# MAIN.net
KiCad netlist of a schematic drawn in Altium Designer
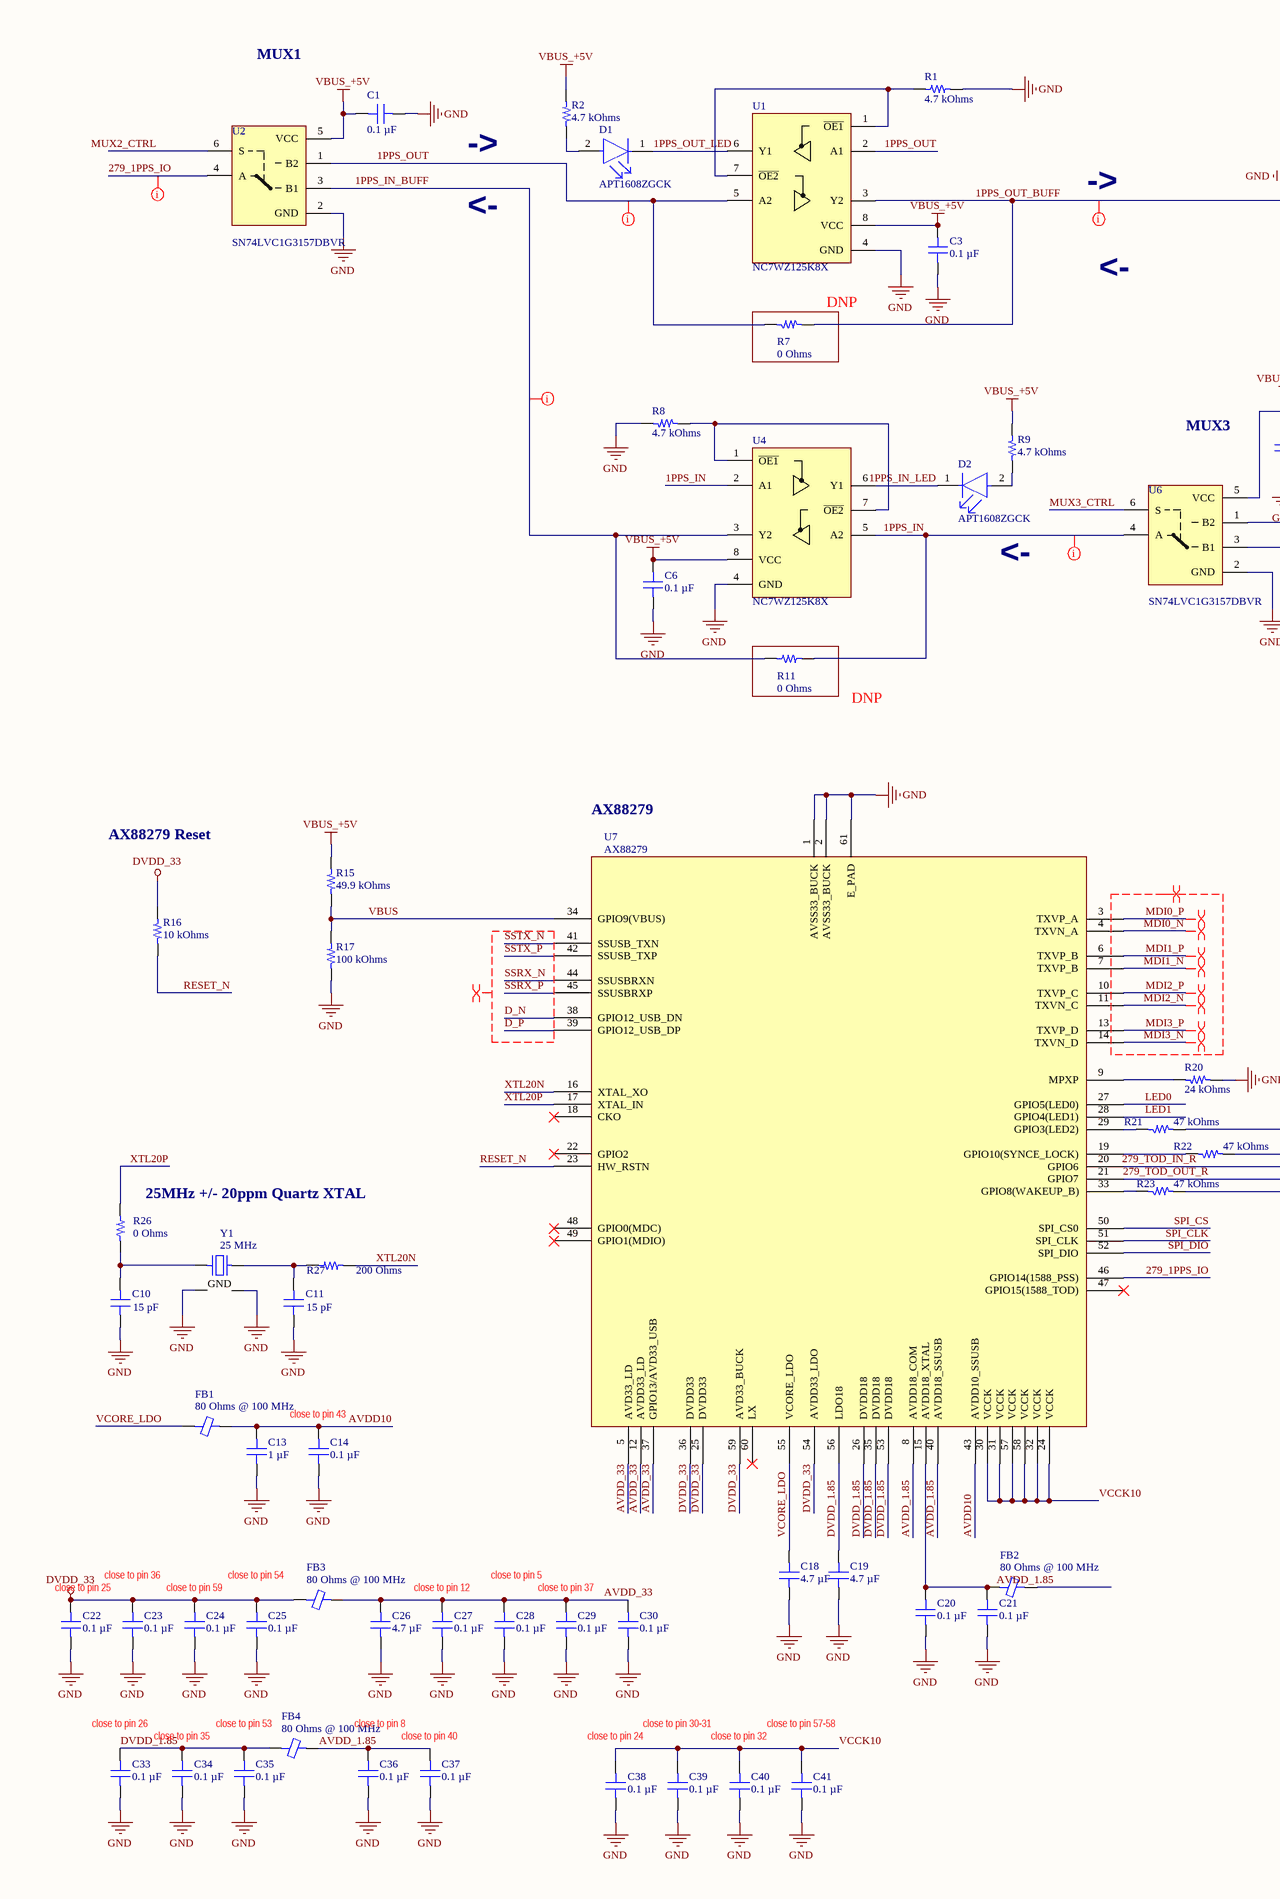
[diagram p0: MAIN.SchDoc, left]
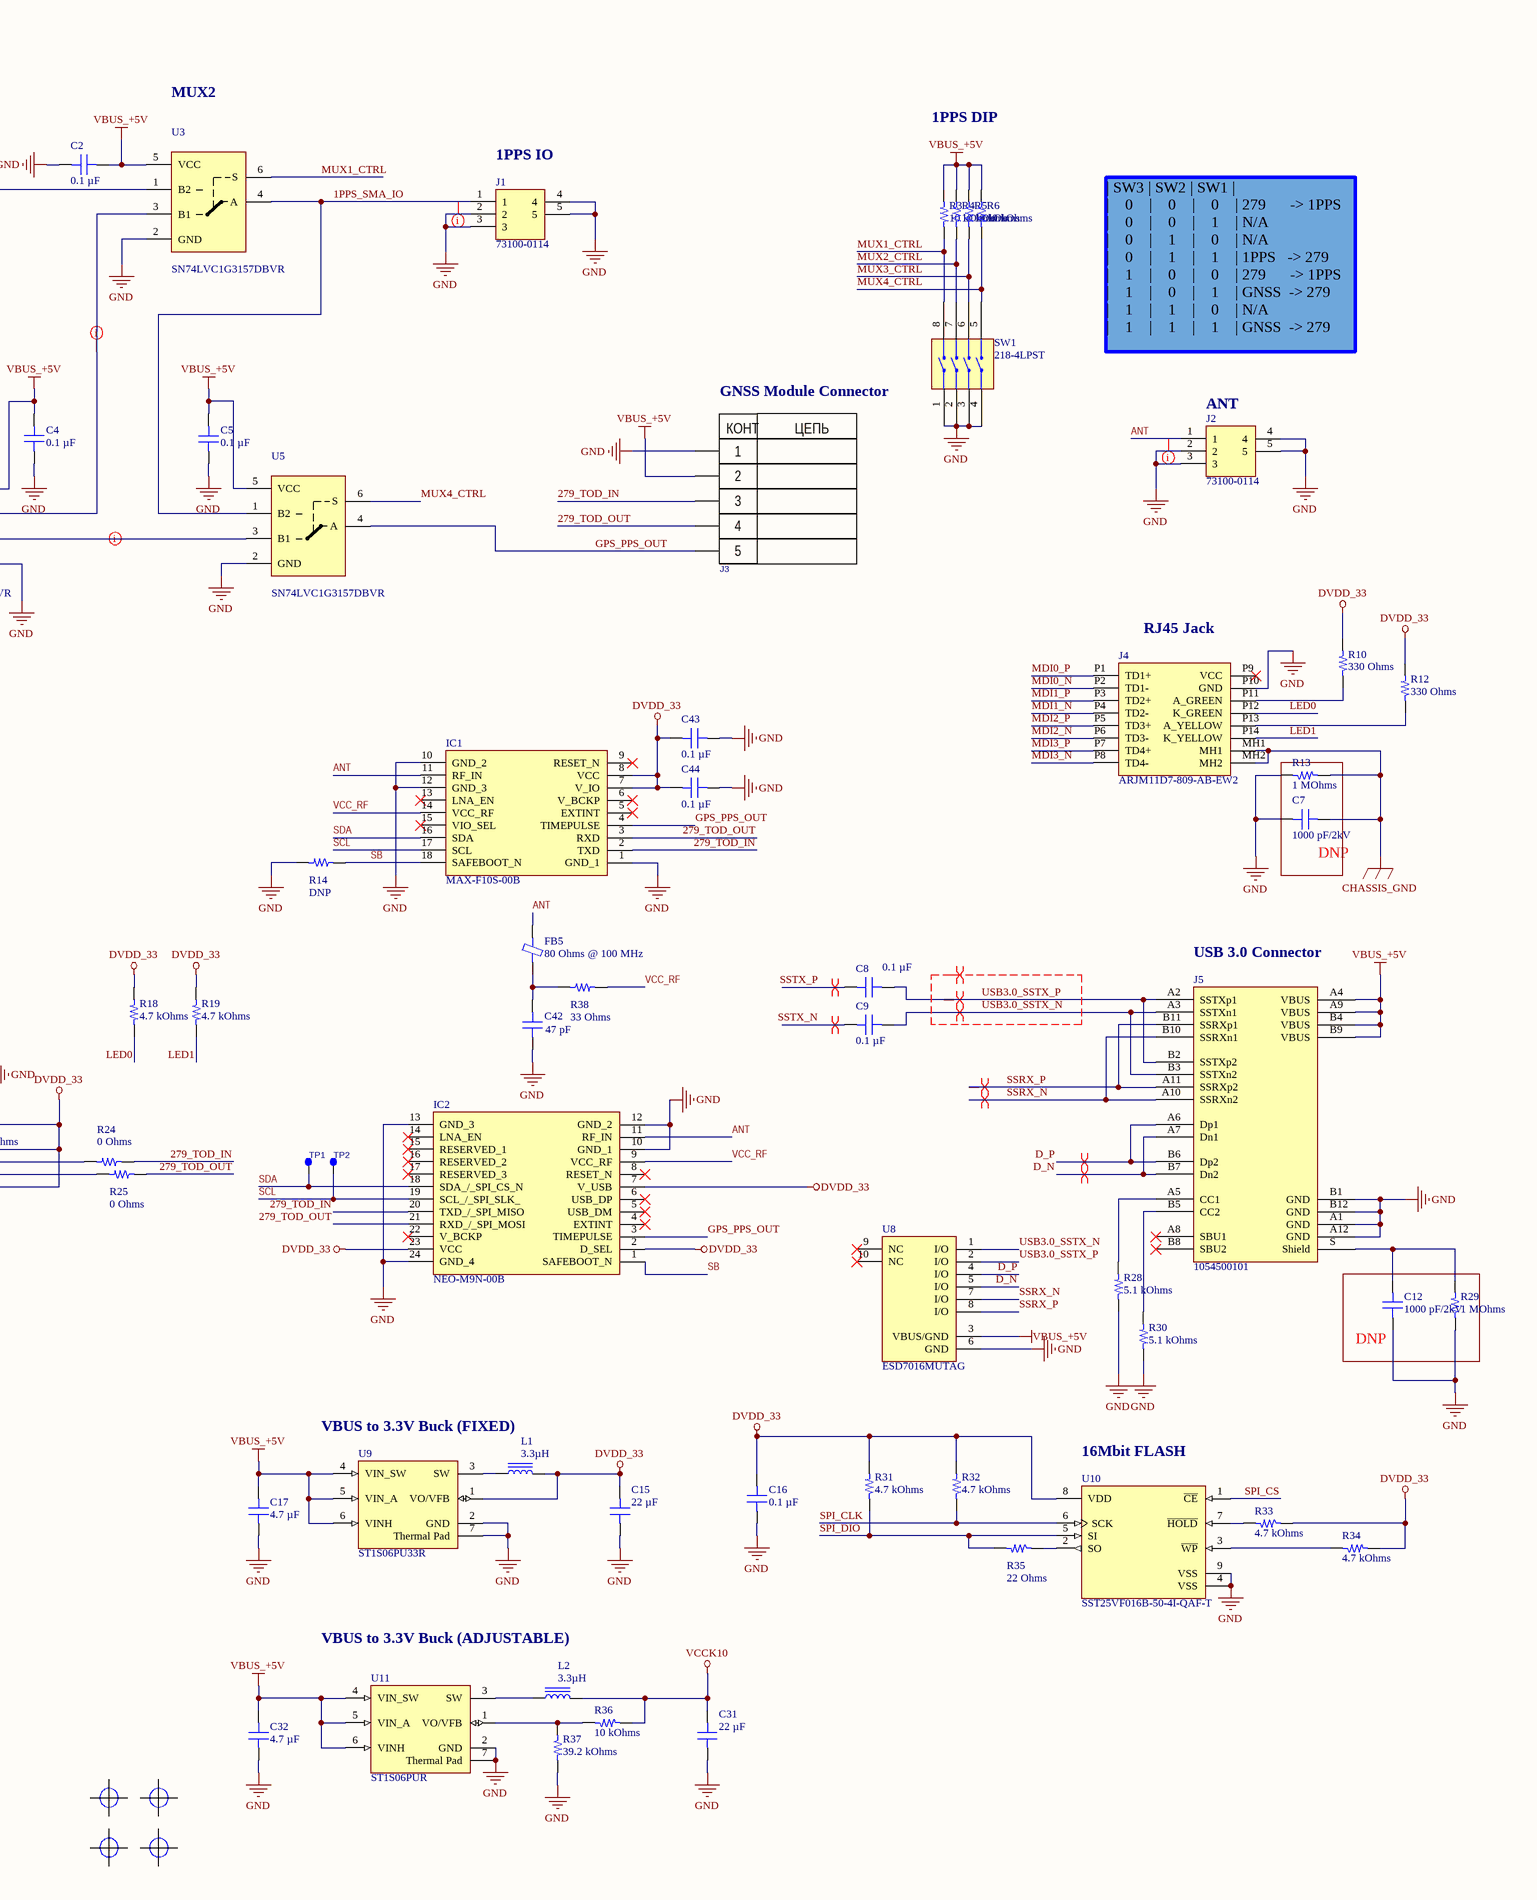
[diagram p1: MAIN.SchDoc, right]

(export (version "E")
  (design (tool "Eeschema 10.0.6"))
  (components
    (comp (ref "C1")
      (value "0.1 µF")
      (footprint "CAP 0402_1005")
      (description "CAP CER 0.1UF 10V X7R 0402")
      (fields (field (name "TOLERANCE") "±10%") (field (name "MANUFACTURER") "Yageo"))
      (libsource (lib "Celestial Altium Library - altium_library") (part "Capacitor"))
    )
    (comp (ref "C2")
      (value "0.1 µF")
      (footprint "CAP 0402_1005")
      (description "CAP CER 0.1UF 10V X7R 0402")
      (fields (field (name "TOLERANCE") "±10%") (field (name "MANUFACTURER") "Yageo"))
      (libsource (lib "Celestial Altium Library - altium_library") (part "Capacitor"))
    )
    (comp (ref "C3")
      (value "0.1 µF")
      (footprint "CAP 0402_1005")
      (description "CAP CER 0.1UF 10V X7R 0402")
      (fields (field (name "TOLERANCE") "±10%") (field (name "MANUFACTURER") "Yageo"))
      (libsource (lib "Celestial Altium Library - altium_library") (part "Capacitor"))
    )
    (comp (ref "C4")
      (value "0.1 µF")
      (footprint "CAP 0402_1005")
      (description "CAP CER 0.1UF 10V X7R 0402")
      (fields (field (name "TOLERANCE") "±10%") (field (name "MANUFACTURER") "Yageo"))
      (libsource (lib "Celestial Altium Library - altium_library") (part "Capacitor"))
    )
    (comp (ref "C5")
      (value "0.1 µF")
      (footprint "CAP 0402_1005")
      (description "CAP CER 0.1UF 10V X7R 0402")
      (fields (field (name "TOLERANCE") "±10%") (field (name "MANUFACTURER") "Yageo"))
      (libsource (lib "Celestial Altium Library - altium_library") (part "Capacitor"))
    )
    (comp (ref "C6")
      (value "0.1 µF")
      (footprint "CAP 0402_1005")
      (description "CAP CER 0.1UF 10V X7R 0402")
      (fields (field (name "TOLERANCE") "±10%") (field (name "MANUFACTURER") "Yageo"))
      (libsource (lib "Celestial Altium Library - altium_library") (part "Capacitor"))
    )
    (comp (ref "C7")
      (value "1000 pF/2kV")
      (footprint "CAP 1206_3216 - 0.8MM")
      (description "CAP CER 1000PF 2KV X7R 1206")
      (fields (field (name "PART NUMBER") "CC1206KKX7RDBB102") (field (name "MANUFACTURER") "Yageo"))
      (libsource (lib "Celestial Altium Library - altium_library") (part "Capacitor"))
    )
    (comp (ref "C8")
      (value "0.1 µF")
      (footprint "CAP 0402_1005")
      (description "CAP CER 0.1UF 10V X7R 0402")
      (fields (field (name "TOLERANCE") "±10%") (field (name "MANUFACTURER") "Yageo"))
      (libsource (lib "Celestial Altium Library - altium_library") (part "Capacitor"))
    )
    (comp (ref "C9")
      (value "0.1 µF")
      (footprint "CAP 0402_1005")
      (description "CAP CER 0.1UF 10V X7R 0402")
      (fields (field (name "TOLERANCE") "±10%") (field (name "MANUFACTURER") "Yageo"))
      (libsource (lib "Celestial Altium Library - altium_library") (part "Capacitor"))
    )
    (comp (ref "C10")
      (value "15 pF")
      (footprint "CAP 0402_1005")
      (description "CAP CER 15PF 50V C0G/NPO 0402")
      (fields (field (name "MANUFACTURER") "Yageo") (field (name "TOLERANCE") "±10%"))
      (libsource (lib "Celestial Altium Library - altium_library") (part "Capacitor"))
    )
    (comp (ref "C11")
      (value "15 pF")
      (footprint "CAP 0402_1005")
      (description "CAP CER 15PF 50V C0G/NPO 0402")
      (fields (field (name "MANUFACTURER") "Yageo") (field (name "TOLERANCE") "±10%"))
      (libsource (lib "Celestial Altium Library - altium_library") (part "Capacitor"))
    )
    (comp (ref "C12")
      (value "1000 pF/2kV")
      (footprint "CAP 1206_3216 - 0.8MM")
      (description "CAP CER 1000PF 2KV X7R 1206")
      (fields (field (name "PART NUMBER") "CC1206KKX7RDBB102") (field (name "MANUFACTURER") "Yageo"))
      (libsource (lib "Celestial Altium Library - altium_library") (part "Capacitor"))
    )
    (comp (ref "C13")
      (value "1 µF")
      (footprint "CAP 0402_1005")
      (description "CAP CER 1UF 10V X5R 0402")
      (fields (field (name "TOLERANCE") "±10%") (field (name "MANUFACTURER") "Yageo"))
      (libsource (lib "Celestial Altium Library - altium_library") (part "Capacitor"))
    )
    (comp (ref "C14")
      (value "0.1 µF")
      (footprint "CAP 0402_1005")
      (description "CAP CER 0.1UF 10V X7R 0402")
      (fields (field (name "TOLERANCE") "±10%") (field (name "MANUFACTURER") "Yageo"))
      (libsource (lib "Celestial Altium Library - altium_library") (part "Capacitor"))
    )
    (comp (ref "C15")
      (value "22 µF")
      (footprint "CAP 0603_1608")
      (description "CAP CER 22UF 10V X5R 0603")
      (fields (field (name "MANUFACTURER") "Yageo") (field (name "TOLERANCE") "±20%"))
      (libsource (lib "Celestial Altium Library - altium_library") (part "Capacitor"))
    )
    (comp (ref "C16")
      (value "0.1 µF")
      (footprint "CAP 0402_1005")
      (description "CAP CER 0.1UF 10V X7R 0402")
      (fields (field (name "TOLERANCE") "±10%") (field (name "MANUFACTURER") "Yageo"))
      (libsource (lib "Celestial Altium Library - altium_library") (part "Capacitor"))
    )
    (comp (ref "C17")
      (value "4.7 µF")
      (footprint "CAP 0402_1005")
      (description "CAP CER 4.7UF 10V X5R 0402")
      (fields (field (name "TOLERANCE") "±20%") (field (name "MANUFACTURER") "Yageo"))
      (libsource (lib "Celestial Altium Library - altium_library") (part "Capacitor"))
    )
    (comp (ref "C18")
      (value "4.7 µF")
      (footprint "CAP 0402_1005")
      (description "CAP CER 4.7UF 10V X5R 0402")
      (fields (field (name "TOLERANCE") "±20%") (field (name "MANUFACTURER") "Yageo"))
      (libsource (lib "Celestial Altium Library - altium_library") (part "Capacitor"))
    )
    (comp (ref "C19")
      (value "4.7 µF")
      (footprint "CAP 0402_1005")
      (description "CAP CER 4.7UF 10V X5R 0402")
      (fields (field (name "TOLERANCE") "±20%") (field (name "MANUFACTURER") "Yageo"))
      (libsource (lib "Celestial Altium Library - altium_library") (part "Capacitor"))
    )
    (comp (ref "C20")
      (value "0.1 µF")
      (footprint "CAP 0402_1005")
      (description "CAP CER 0.1UF 10V X7R 0402")
      (fields (field (name "TOLERANCE") "±10%") (field (name "MANUFACTURER") "Yageo"))
      (libsource (lib "Celestial Altium Library - altium_library") (part "Capacitor"))
    )
    (comp (ref "C21")
      (value "0.1 µF")
      (footprint "CAP 0402_1005")
      (description "CAP CER 0.1UF 10V X7R 0402")
      (fields (field (name "TOLERANCE") "±10%") (field (name "MANUFACTURER") "Yageo"))
      (libsource (lib "Celestial Altium Library - altium_library") (part "Capacitor"))
    )
    (comp (ref "C22")
      (value "0.1 µF")
      (footprint "CAP 0402_1005")
      (description "CAP CER 0.1UF 10V X7R 0402")
      (fields (field (name "TOLERANCE") "±10%") (field (name "MANUFACTURER") "Yageo"))
      (libsource (lib "Celestial Altium Library - altium_library") (part "Capacitor"))
    )
    (comp (ref "C23")
      (value "0.1 µF")
      (footprint "CAP 0402_1005")
      (description "CAP CER 0.1UF 10V X7R 0402")
      (fields (field (name "TOLERANCE") "±10%") (field (name "MANUFACTURER") "Yageo"))
      (libsource (lib "Celestial Altium Library - altium_library") (part "Capacitor"))
    )
    (comp (ref "C24")
      (value "0.1 µF")
      (footprint "CAP 0402_1005")
      (description "CAP CER 0.1UF 10V X7R 0402")
      (fields (field (name "TOLERANCE") "±10%") (field (name "MANUFACTURER") "Yageo"))
      (libsource (lib "Celestial Altium Library - altium_library") (part "Capacitor"))
    )
    (comp (ref "C25")
      (value "0.1 µF")
      (footprint "CAP 0402_1005")
      (description "CAP CER 0.1UF 10V X7R 0402")
      (fields (field (name "TOLERANCE") "±10%") (field (name "MANUFACTURER") "Yageo"))
      (libsource (lib "Celestial Altium Library - altium_library") (part "Capacitor"))
    )
    (comp (ref "C26")
      (value "4.7 µF")
      (footprint "CAP 0402_1005")
      (description "CAP CER 4.7UF 10V X5R 0402")
      (fields (field (name "TOLERANCE") "±20%") (field (name "MANUFACTURER") "Yageo"))
      (libsource (lib "Celestial Altium Library - altium_library") (part "Capacitor"))
    )
    (comp (ref "C27")
      (value "0.1 µF")
      (footprint "CAP 0402_1005")
      (description "CAP CER 0.1UF 10V X7R 0402")
      (fields (field (name "TOLERANCE") "±10%") (field (name "MANUFACTURER") "Yageo"))
      (libsource (lib "Celestial Altium Library - altium_library") (part "Capacitor"))
    )
    (comp (ref "C28")
      (value "0.1 µF")
      (footprint "CAP 0402_1005")
      (description "CAP CER 0.1UF 10V X7R 0402")
      (fields (field (name "TOLERANCE") "±10%") (field (name "MANUFACTURER") "Yageo"))
      (libsource (lib "Celestial Altium Library - altium_library") (part "Capacitor"))
    )
    (comp (ref "C29")
      (value "0.1 µF")
      (footprint "CAP 0402_1005")
      (description "CAP CER 0.1UF 10V X7R 0402")
      (fields (field (name "TOLERANCE") "±10%") (field (name "MANUFACTURER") "Yageo"))
      (libsource (lib "Celestial Altium Library - altium_library") (part "Capacitor"))
    )
    (comp (ref "C30")
      (value "0.1 µF")
      (footprint "CAP 0402_1005")
      (description "CAP CER 0.1UF 10V X7R 0402")
      (fields (field (name "TOLERANCE") "±10%") (field (name "MANUFACTURER") "Yageo"))
      (libsource (lib "Celestial Altium Library - altium_library") (part "Capacitor"))
    )
    (comp (ref "C31")
      (value "22 µF")
      (footprint "CAP 0603_1608")
      (description "CAP CER 22UF 10V X5R 0603")
      (fields (field (name "MANUFACTURER") "Yageo") (field (name "TOLERANCE") "±20%"))
      (libsource (lib "Celestial Altium Library - altium_library") (part "Capacitor"))
    )
    (comp (ref "C32")
      (value "4.7 µF")
      (footprint "CAP 0402_1005")
      (description "CAP CER 4.7UF 10V X5R 0402")
      (fields (field (name "TOLERANCE") "±20%") (field (name "MANUFACTURER") "Yageo"))
      (libsource (lib "Celestial Altium Library - altium_library") (part "Capacitor"))
    )
    (comp (ref "C33")
      (value "0.1 µF")
      (footprint "CAP 0402_1005")
      (description "CAP CER 0.1UF 10V X7R 0402")
      (fields (field (name "TOLERANCE") "±10%") (field (name "MANUFACTURER") "Yageo"))
      (libsource (lib "Celestial Altium Library - altium_library") (part "Capacitor"))
    )
    (comp (ref "C34")
      (value "0.1 µF")
      (footprint "CAP 0402_1005")
      (description "CAP CER 0.1UF 10V X7R 0402")
      (fields (field (name "TOLERANCE") "±10%") (field (name "MANUFACTURER") "Yageo"))
      (libsource (lib "Celestial Altium Library - altium_library") (part "Capacitor"))
    )
    (comp (ref "C35")
      (value "0.1 µF")
      (footprint "CAP 0402_1005")
      (description "CAP CER 0.1UF 10V X7R 0402")
      (fields (field (name "TOLERANCE") "±10%") (field (name "MANUFACTURER") "Yageo"))
      (libsource (lib "Celestial Altium Library - altium_library") (part "Capacitor"))
    )
    (comp (ref "C36")
      (value "0.1 µF")
      (footprint "CAP 0402_1005")
      (description "CAP CER 0.1UF 10V X7R 0402")
      (fields (field (name "TOLERANCE") "±10%") (field (name "MANUFACTURER") "Yageo"))
      (libsource (lib "Celestial Altium Library - altium_library") (part "Capacitor"))
    )
    (comp (ref "C37")
      (value "0.1 µF")
      (footprint "CAP 0402_1005")
      (description "CAP CER 0.1UF 10V X7R 0402")
      (fields (field (name "TOLERANCE") "±10%") (field (name "MANUFACTURER") "Yageo"))
      (libsource (lib "Celestial Altium Library - altium_library") (part "Capacitor"))
    )
    (comp (ref "C38")
      (value "0.1 µF")
      (footprint "CAP 0402_1005")
      (description "CAP CER 0.1UF 10V X7R 0402")
      (fields (field (name "TOLERANCE") "±10%") (field (name "MANUFACTURER") "Yageo"))
      (libsource (lib "Celestial Altium Library - altium_library") (part "Capacitor"))
    )
    (comp (ref "C39")
      (value "0.1 µF")
      (footprint "CAP 0402_1005")
      (description "CAP CER 0.1UF 10V X7R 0402")
      (fields (field (name "TOLERANCE") "±10%") (field (name "MANUFACTURER") "Yageo"))
      (libsource (lib "Celestial Altium Library - altium_library") (part "Capacitor"))
    )
    (comp (ref "C40")
      (value "0.1 µF")
      (footprint "CAP 0402_1005")
      (description "CAP CER 0.1UF 10V X7R 0402")
      (fields (field (name "TOLERANCE") "±10%") (field (name "MANUFACTURER") "Yageo"))
      (libsource (lib "Celestial Altium Library - altium_library") (part "Capacitor"))
    )
    (comp (ref "C41")
      (value "0.1 µF")
      (footprint "CAP 0402_1005")
      (description "CAP CER 0.1UF 10V X7R 0402")
      (fields (field (name "TOLERANCE") "±10%") (field (name "MANUFACTURER") "Yageo"))
      (libsource (lib "Celestial Altium Library - altium_library") (part "Capacitor"))
    )
    (comp (ref "C42")
      (value "47 pF")
      (footprint "CAP 0402_1005")
      (description "CAP CER 47PF 50V C0G/NPO 0402")
      (fields (field (name "MANUFACTURER") "Yageo") (field (name "TOLERANCE") "±10%"))
      (libsource (lib "Celestial Altium Library - altium_library") (part "Capacitor"))
    )
    (comp (ref "C43")
      (value "0.1 µF")
      (footprint "CAP 0402_1005")
      (description "CAP CER 0.1UF 10V X7R 0402")
      (fields (field (name "TOLERANCE") "±10%") (field (name "MANUFACTURER") "Yageo"))
      (libsource (lib "Celestial Altium Library - altium_library") (part "Capacitor"))
    )
    (comp (ref "C44")
      (value "0.1 µF")
      (footprint "CAP 0402_1005")
      (description "CAP CER 0.1UF 10V X7R 0402")
      (fields (field (name "TOLERANCE") "±10%") (field (name "MANUFACTURER") "Yageo"))
      (libsource (lib "Celestial Altium Library - altium_library") (part "Capacitor"))
    )
    (comp (ref "D1")
      (value "APT1608ZGCK")
      (footprint "FP-APT1608ZGCK-MFG")
      (description "LED GREEN CLEAR CHIP SMD")
      (fields (field (name "MANUFACTURER") "Kingbright"))
      (libsource (lib "Altium Content Vault") (part "8706943c75ba83719d021d2fdc84c58"))
    )
    (comp (ref "D2")
      (value "APT1608ZGCK")
      (footprint "FP-APT1608ZGCK-MFG")
      (description "LED GREEN CLEAR CHIP SMD")
      (fields (field (name "MANUFACTURER") "Kingbright"))
      (libsource (lib "Altium Content Vault") (part "8706943c75ba83719d021d2fdc84c58"))
    )
    (comp (ref "FB1")
      (value "80 Ohms @ 100 MHz")
      (footprint "FER 0402_1005")
      (description "FERRITE BEAD 80 OHM 0402 1LN")
      (fields
        (field (name "MANUFACTURER") "Murata Electronics")
        (field (name "PART NUMBER") "BLM15PD800SN1D")
      )
      (libsource (lib "Celestial Altium Library - altium_library") (part "Ferrite Chip"))
    )
    (comp (ref "FB2")
      (value "80 Ohms @ 100 MHz")
      (footprint "FER 0402_1005")
      (description "FERRITE BEAD 80 OHM 0402 1LN")
      (fields
        (field (name "MANUFACTURER") "Murata Electronics")
        (field (name "PART NUMBER") "BLM15PD800SN1D")
      )
      (libsource (lib "Celestial Altium Library - altium_library") (part "Ferrite Chip"))
    )
    (comp (ref "FB3")
      (value "80 Ohms @ 100 MHz")
      (footprint "FER 0402_1005")
      (description "FERRITE BEAD 80 OHM 0402 1LN")
      (fields
        (field (name "MANUFACTURER") "Murata Electronics")
        (field (name "PART NUMBER") "BLM15PD800SN1D")
      )
      (libsource (lib "Celestial Altium Library - altium_library") (part "Ferrite Chip"))
    )
    (comp (ref "FB4")
      (value "80 Ohms @ 100 MHz")
      (footprint "FER 0402_1005")
      (description "FERRITE BEAD 80 OHM 0402 1LN")
      (fields
        (field (name "MANUFACTURER") "Murata Electronics")
        (field (name "PART NUMBER") "BLM15PD800SN1D")
      )
      (libsource (lib "Celestial Altium Library - altium_library") (part "Ferrite Chip"))
    )
    (comp (ref "FB5")
      (value "80 Ohms @ 100 MHz")
      (footprint "FER 0402_1005")
      (description "FERRITE BEAD 80 OHM 0402 1LN")
      (fields
        (field (name "MANUFACTURER") "Murata Electronics")
        (field (name "PART NUMBER") "BLM15PD800SN1D")
      )
      (libsource (lib "Celestial Altium Library - altium_library") (part "Ferrite Chip"))
    )
    (comp (ref "IC1")
      (value "MAX-F10S-00B")
      (footprint "SamacSys:MAXF10S00B")
      (description "Integrated Circuit")
      (libsource (lib "SamacSys") (part "MAX-F10S-00B"))
    )
    (comp (ref "IC2")
      (value "NEO-M9N-00B")
      (footprint "SamacSys:NEOM9N00B")
      (description "Integrated Circuit")
      (fields (field (name "MOUSER PART NUMBER") "377-NEO-M9N-00B"))
      (libsource (lib "SamacSys") (part "NEO-M9N-00B"))
    )
    (comp (ref "J1")
      (value "73100-0114")
      (footprint "SamacSys:731000114")
      (description "Connector")
      (fields (field (name "MOUSER PART NUMBER") "538-73100-0114"))
      (libsource (lib "SamacSys") (part "73100-0114"))
    )
    (comp (ref "J2")
      (value "73100-0114")
      (footprint "SamacSys:731000114")
      (description "Connector")
      (fields (field (name "MOUSER PART NUMBER") "538-73100-0114"))
      (libsource (lib "SamacSys") (part "73100-0114"))
    )
    (comp (ref "J3")
      (value "PBS-5")
      (footprint "SamacSys:PBS-5")
      (description "Connector")
      (fields (field (name "MANUFACTURER") "Connfly") (field (name "PART NUMBER") "PBD-5"))
      (libsource (lib "SamacSys") (part "PBS-5"))
    )
    (comp (ref "J4")
      (value "ARJM11D7-809-AB-EW2")
      (footprint "SamacSys:ARJM11D7809ABEW2")
      (description "Connector")
      (fields (field (name "MOUSER PART NUMBER") "815-RJM11D7809ABEW2"))
      (libsource (lib "*") (part "ARJM11D7-809-AB-EW2"))
    )
    (comp (ref "J5")
      (value "1054500101")
      (footprint "Molex 1054500101")
      (description "CONN RCP USB3.1 TYPEC 24P SMD RA")
      (fields (field (name "MANUFACTURER") "Molex"))
      (libsource (lib "Celestial Altium Library - altium_library") (part "USB 3.0 Type C"))
    )
    (comp (ref "L1")
      (value "3.3µH")
      (footprint "IND 1008_2520")
      (description "FIXED IND 3.3UH 1.2A 100 MOHM")
      (fields (field (name "TOLERANCE") "±20%") (field (name "MANUFACTURER") "Murata Electronics"))
      (libsource (lib "Celestial Altium Library - altium_library") (part "Inductor"))
    )
    (comp (ref "L2")
      (value "3.3µH")
      (footprint "IND 1008_2520")
      (description "FIXED IND 3.3UH 1.2A 100 MOHM")
      (fields (field (name "TOLERANCE") "±20%") (field (name "MANUFACTURER") "Murata Electronics"))
      (libsource (lib "Celestial Altium Library - altium_library") (part "Inductor"))
    )
    (comp (ref "MNT1")
      (value "MOUNT_HOLE")
      (footprint "SamacSys:MOUNT_3mm")
      (description "Mount hole")
      (libsource (lib "SamacSys") (part "MOUNT_HOLE"))
    )
    (comp (ref "MNT2")
      (value "MOUNT_HOLE")
      (footprint "SamacSys:MOUNT_3mm")
      (description "Mount hole")
      (libsource (lib "SamacSys") (part "MOUNT_HOLE"))
    )
    (comp (ref "MNT3")
      (value "MOUNT_HOLE")
      (footprint "SamacSys:MOUNT_3mm")
      (description "Mount hole")
      (libsource (lib "SamacSys") (part "MOUNT_HOLE"))
    )
    (comp (ref "MNT4")
      (value "MOUNT_HOLE")
      (footprint "SamacSys:MOUNT_3mm")
      (description "Mount hole")
      (libsource (lib "SamacSys") (part "MOUNT_HOLE"))
    )
    (comp (ref "R1")
      (value "4.7 kOhms")
      (footprint "YAGEO RES 0402_1005")
      (description "RES 4.7K OHM 1% 1/16W 0402")
      (fields (field (name "TOLERANCE") "±1%") (field (name "MANUFACTURER") "Yageo"))
      (libsource (lib "Celestial Altium Library - altium_library") (part "Resistor"))
    )
    (comp (ref "R2")
      (value "4.7 kOhms")
      (footprint "YAGEO RES 0402_1005")
      (description "RES 4.7K OHM 1% 1/16W 0402")
      (fields (field (name "TOLERANCE") "±1%") (field (name "MANUFACTURER") "Yageo"))
      (libsource (lib "Celestial Altium Library - altium_library") (part "Resistor"))
    )
    (comp (ref "R3")
      (value "10 kOhms")
      (footprint "YAGEO RES 0402_1005")
      (description "RES 10K OHM 1% 1/16W 0402")
      (fields (field (name "TOLERANCE") "±1%") (field (name "MANUFACTURER") "Yageo"))
      (libsource (lib "Celestial Altium Library - altium_library") (part "Resistor"))
    )
    (comp (ref "R4")
      (value "10 kOhms")
      (footprint "YAGEO RES 0402_1005")
      (description "RES 10K OHM 1% 1/16W 0402")
      (fields (field (name "TOLERANCE") "±1%") (field (name "MANUFACTURER") "Yageo"))
      (libsource (lib "Celestial Altium Library - altium_library") (part "Resistor"))
    )
    (comp (ref "R5")
      (value "10 kOhms")
      (footprint "YAGEO RES 0402_1005")
      (description "RES 10K OHM 1% 1/16W 0402")
      (fields (field (name "TOLERANCE") "±1%") (field (name "MANUFACTURER") "Yageo"))
      (libsource (lib "Celestial Altium Library - altium_library") (part "Resistor"))
    )
    (comp (ref "R6")
      (value "10 kOhms")
      (footprint "YAGEO RES 0402_1005")
      (description "RES 10K OHM 1% 1/16W 0402")
      (fields (field (name "TOLERANCE") "±1%") (field (name "MANUFACTURER") "Yageo"))
      (libsource (lib "Celestial Altium Library - altium_library") (part "Resistor"))
    )
    (comp (ref "R7")
      (value "0 Ohms")
      (footprint "YAGEO RES 0402_1005")
      (description "RES 0 OHM JUMPER 1/16W 0402")
      (fields (field (name "TOLERANCE") "Jumper") (field (name "MANUFACTURER") "Yageo"))
      (libsource (lib "Celestial Altium Library - altium_library") (part "Resistor"))
    )
    (comp (ref "R8")
      (value "4.7 kOhms")
      (footprint "YAGEO RES 0402_1005")
      (description "RES 4.7K OHM 1% 1/16W 0402")
      (fields (field (name "TOLERANCE") "±1%") (field (name "MANUFACTURER") "Yageo"))
      (libsource (lib "Celestial Altium Library - altium_library") (part "Resistor"))
    )
    (comp (ref "R9")
      (value "4.7 kOhms")
      (footprint "YAGEO RES 0402_1005")
      (description "RES 4.7K OHM 1% 1/16W 0402")
      (fields (field (name "TOLERANCE") "±1%") (field (name "MANUFACTURER") "Yageo"))
      (libsource (lib "Celestial Altium Library - altium_library") (part "Resistor"))
    )
    (comp (ref "R10")
      (value "330 Ohms")
      (footprint "YAGEO RES 0402_1005")
      (description "RES 330 OHM 1% 1/16W 0402")
      (fields (field (name "TOLERANCE") "±1%") (field (name "MANUFACTURER") "Yageo"))
      (libsource (lib "Celestial Altium Library - altium_library") (part "Resistor"))
    )
    (comp (ref "R11")
      (value "0 Ohms")
      (footprint "YAGEO RES 0402_1005")
      (description "RES 0 OHM JUMPER 1/16W 0402")
      (fields (field (name "TOLERANCE") "Jumper") (field (name "MANUFACTURER") "Yageo"))
      (libsource (lib "Celestial Altium Library - altium_library") (part "Resistor"))
    )
    (comp (ref "R12")
      (value "330 Ohms")
      (footprint "YAGEO RES 0402_1005")
      (description "RES 330 OHM 1% 1/16W 0402")
      (fields (field (name "TOLERANCE") "±1%") (field (name "MANUFACTURER") "Yageo"))
      (libsource (lib "Celestial Altium Library - altium_library") (part "Resistor"))
    )
    (comp (ref "R13")
      (value "1 MOhms")
      (footprint "YAGEO RES 0402_1005")
      (description "RES 1M OHM 1% 1/16W 0402")
      (fields (field (name "TOLERANCE") "±1%") (field (name "MANUFACTURER") "Yageo"))
      (libsource (lib "Celestial Altium Library - altium_library") (part "Resistor"))
    )
    (comp (ref "R14")
      (value "DNP")
      (footprint "YAGEO RES 0402_1005")
      (description "RES 0 OHM JUMPER 1/16W 0402")
      (fields (field (name "TOLERANCE") "Jumper") (field (name "MANUFACTURER") "Yageo"))
      (libsource (lib "Celestial Altium Library - altium_library") (part "Resistor"))
    )
    (comp (ref "R15")
      (value "49.9 kOhms")
      (footprint "YAGEO RES 0402_1005")
      (description "RES 49.9K OHM 1% 1/16W 0402")
      (fields (field (name "TOLERANCE") "±1%") (field (name "MANUFACTURER") "Yageo"))
      (libsource (lib "Celestial Altium Library - altium_library") (part "Resistor"))
    )
    (comp (ref "R16")
      (value "10 kOhms")
      (footprint "YAGEO RES 0402_1005")
      (description "RES 10K OHM 1% 1/16W 0402")
      (fields (field (name "TOLERANCE") "±1%") (field (name "MANUFACTURER") "Yageo"))
      (libsource (lib "Celestial Altium Library - altium_library") (part "Resistor"))
    )
    (comp (ref "R17")
      (value "100 kOhms")
      (footprint "YAGEO RES 0402_1005")
      (description "RES 100K OHM 1% 1/16W 0402")
      (fields (field (name "TOLERANCE") "±1%") (field (name "MANUFACTURER") "Yageo"))
      (libsource (lib "Celestial Altium Library - altium_library") (part "Resistor"))
    )
    (comp (ref "R18")
      (value "4.7 kOhms")
      (footprint "YAGEO RES 0402_1005")
      (description "RES 4.7K OHM 1% 1/16W 0402")
      (fields (field (name "TOLERANCE") "±1%") (field (name "MANUFACTURER") "Yageo"))
      (libsource (lib "Celestial Altium Library - altium_library") (part "Resistor"))
    )
    (comp (ref "R19")
      (value "4.7 kOhms")
      (footprint "YAGEO RES 0402_1005")
      (description "RES 4.7K OHM 1% 1/16W 0402")
      (fields (field (name "TOLERANCE") "±1%") (field (name "MANUFACTURER") "Yageo"))
      (libsource (lib "Celestial Altium Library - altium_library") (part "Resistor"))
    )
    (comp (ref "R20")
      (value "24 kOhms")
      (footprint "YAGEO RES 0402_1005")
      (description "RES 24K OHM 1% 1/16W 0402")
      (fields (field (name "TOLERANCE") "±1%") (field (name "MANUFACTURER") "Yageo"))
      (libsource (lib "Celestial Altium Library - altium_library") (part "Resistor"))
    )
    (comp (ref "R21")
      (value "47 kOhms")
      (footprint "YAGEO RES 0402_1005")
      (description "RES 47K OHM 1% 1/16W 0402")
      (fields (field (name "TOLERANCE") "±1%") (field (name "MANUFACTURER") "Yageo"))
      (libsource (lib "Celestial Altium Library - altium_library") (part "Resistor"))
    )
    (comp (ref "R22")
      (value "47 kOhms")
      (footprint "YAGEO RES 0402_1005")
      (description "RES 47K OHM 1% 1/16W 0402")
      (fields (field (name "TOLERANCE") "±1%") (field (name "MANUFACTURER") "Yageo"))
      (libsource (lib "Celestial Altium Library - altium_library") (part "Resistor"))
    )
    (comp (ref "R23")
      (value "47 kOhms")
      (footprint "YAGEO RES 0402_1005")
      (description "RES 47K OHM 1% 1/16W 0402")
      (fields (field (name "TOLERANCE") "±1%") (field (name "MANUFACTURER") "Yageo"))
      (libsource (lib "Celestial Altium Library - altium_library") (part "Resistor"))
    )
    (comp (ref "R24")
      (value "0 Ohms")
      (footprint "YAGEO RES 0402_1005")
      (description "RES 0 OHM JUMPER 1/16W 0402")
      (fields (field (name "TOLERANCE") "Jumper") (field (name "MANUFACTURER") "Yageo"))
      (libsource (lib "Celestial Altium Library - altium_library") (part "Resistor"))
    )
    (comp (ref "R25")
      (value "0 Ohms")
      (footprint "YAGEO RES 0402_1005")
      (description "RES 0 OHM JUMPER 1/16W 0402")
      (fields (field (name "TOLERANCE") "Jumper") (field (name "MANUFACTURER") "Yageo"))
      (libsource (lib "Celestial Altium Library - altium_library") (part "Resistor"))
    )
    (comp (ref "R26")
      (value "0 Ohms")
      (footprint "YAGEO RES 0402_1005")
      (description "RES 0 OHM JUMPER 1/16W 0402")
      (fields (field (name "TOLERANCE") "Jumper") (field (name "MANUFACTURER") "Yageo"))
      (libsource (lib "Celestial Altium Library - altium_library") (part "Resistor"))
    )
    (comp (ref "R27")
      (value "200 Ohms")
      (footprint "YAGEO RES 0402_1005")
      (description "RES 200 OHM 1% 1/16W 0402")
      (fields (field (name "MANUFACTURER") "Yageo") (field (name "PART NUMBER") "RC0402FR-07200RL"))
      (libsource (lib "Celestial Altium Library - altium_library") (part "Resistor"))
    )
    (comp (ref "R28")
      (value "5.1 kOhms")
      (footprint "YAGEO RES 0402_1005")
      (description "RES 5.1K OHM 1% 1/16W 0402")
      (fields (field (name "TOLERANCE") "±1%") (field (name "MANUFACTURER") "Yageo"))
      (libsource (lib "Celestial Altium Library - altium_library") (part "Resistor"))
    )
    (comp (ref "R29")
      (value "1 MOhms")
      (footprint "YAGEO RES 0402_1005")
      (description "RES 1M OHM 1% 1/16W 0402")
      (fields (field (name "TOLERANCE") "±1%") (field (name "MANUFACTURER") "Yageo"))
      (libsource (lib "Celestial Altium Library - altium_library") (part "Resistor"))
    )
    (comp (ref "R30")
      (value "5.1 kOhms")
      (footprint "YAGEO RES 0402_1005")
      (description "RES 5.1K OHM 1% 1/16W 0402")
      (fields (field (name "TOLERANCE") "±1%") (field (name "MANUFACTURER") "Yageo"))
      (libsource (lib "Celestial Altium Library - altium_library") (part "Resistor"))
    )
    (comp (ref "R31")
      (value "4.7 kOhms")
      (footprint "YAGEO RES 0402_1005")
      (description "RES 4.7K OHM 1% 1/16W 0402")
      (fields (field (name "TOLERANCE") "±1%") (field (name "MANUFACTURER") "Yageo"))
      (libsource (lib "Celestial Altium Library - altium_library") (part "Resistor"))
    )
    (comp (ref "R32")
      (value "4.7 kOhms")
      (footprint "YAGEO RES 0402_1005")
      (description "RES 4.7K OHM 1% 1/16W 0402")
      (fields (field (name "TOLERANCE") "±1%") (field (name "MANUFACTURER") "Yageo"))
      (libsource (lib "Celestial Altium Library - altium_library") (part "Resistor"))
    )
    (comp (ref "R33")
      (value "4.7 kOhms")
      (footprint "YAGEO RES 0402_1005")
      (description "RES 4.7K OHM 1% 1/16W 0402")
      (fields (field (name "TOLERANCE") "±1%") (field (name "MANUFACTURER") "Yageo"))
      (libsource (lib "Celestial Altium Library - altium_library") (part "Resistor"))
    )
    (comp (ref "R34")
      (value "4.7 kOhms")
      (footprint "YAGEO RES 0402_1005")
      (description "RES 4.7K OHM 1% 1/16W 0402")
      (fields (field (name "TOLERANCE") "±1%") (field (name "MANUFACTURER") "Yageo"))
      (libsource (lib "Celestial Altium Library - altium_library") (part "Resistor"))
    )
    (comp (ref "R35")
      (value "22 Ohms")
      (footprint "YAGEO RES 0402_1005")
      (description "RES 22 OHM 1% 1/16W 0402")
      (fields (field (name "TOLERANCE") "±1%") (field (name "MANUFACTURER") "Yageo"))
      (libsource (lib "Celestial Altium Library - altium_library") (part "Resistor"))
    )
    (comp (ref "R36")
      (value "10 kOhms")
      (footprint "YAGEO RES 0402_1005")
      (description "RES 10K OHM 1% 1/16W 0402")
      (fields (field (name "TOLERANCE") "±1%") (field (name "MANUFACTURER") "Yageo"))
      (libsource (lib "Celestial Altium Library - altium_library") (part "Resistor"))
    )
    (comp (ref "R37")
      (value "39.2 kOhms")
      (footprint "YAGEO RES 0402_1005")
      (description "RES 39.2K OHM 1% 1/16W 0402")
      (fields (field (name "TOLERANCE") "±1%") (field (name "MANUFACTURER") "Yageo"))
      (libsource (lib "Celestial Altium Library - altium_library") (part "Resistor"))
    )
    (comp (ref "R38")
      (value "33 Ohms")
      (footprint "YAGEO RES 0402_1005")
      (description "RES 33 OHM 1% 1/16W 0402")
      (fields (field (name "TOLERANCE") "±1%") (field (name "MANUFACTURER") "Yageo"))
      (libsource (lib "Celestial Altium Library - altium_library") (part "Resistor"))
    )
    (comp (ref "SW1")
      (value "218-4LPST")
      (footprint "CTS 218-4LPJ")
      (description "SWITCH SLIDE DIP SPST 25MA 24V")
      (fields (field (name "MANUFACTURER") "CTS Electrocomponents"))
      (libsource (lib "Celestial Altium Library - altium_library") (part "DIP SW 4P"))
    )
    (comp (ref "TP1")
      (value "PAD_TEST")
      (footprint "Samacsys:PAD_TEST")
      (description "Test Point")
      (fields (field (name "TOLERANCE") "{Tolerance}") (field (name "MANUFACTURER") "{Manufacturer}"))
      (libsource (lib "SamacSys") (part "PAD_TEST"))
    )
    (comp (ref "TP2")
      (value "PAD_TEST")
      (footprint "Samacsys:PAD_TEST")
      (description "Test Point")
      (fields (field (name "TOLERANCE") "{Tolerance}") (field (name "MANUFACTURER") "{Manufacturer}"))
      (libsource (lib "SamacSys") (part "PAD_TEST"))
    )
    (comp (ref "U1")
      (value "NC7WZ125K8X")
      (footprint "SamacSys:SOP50P310X90-8N")
      (description "Integrated Circuit")
      (libsource (lib "") (part "NC7WZ125K8X_1"))
    )
    (comp (ref "U2")
      (value "SN74LVC1G3157DBVR")
      (footprint "SamacSys:SOT95P280X145-6N")
      (description "Integrated Circuit")
      (fields (field (name "MOUSER PART NUMBER") "595-SN74LVC1G3157DBV"))
      (libsource (lib "") (part "SN74LVC1G3157DBVR_1"))
    )
    (comp (ref "U3")
      (value "SN74LVC1G3157DBVR")
      (footprint "SamacSys:SOT95P280X145-6N")
      (description "Integrated Circuit")
      (fields (field (name "MOUSER PART NUMBER") "595-SN74LVC1G3157DBV"))
      (libsource (lib "SamacSys") (part "SN74LVC1G3157DBVR"))
    )
    (comp (ref "U4")
      (value "NC7WZ125K8X")
      (footprint "SamacSys:SOP50P310X90-8N")
      (description "Integrated Circuit")
      (libsource (lib "SamacSys") (part "NC7WZ125K8X"))
    )
    (comp (ref "U5")
      (value "SN74LVC1G3157DBVR")
      (footprint "SamacSys:SOT95P280X145-6N")
      (description "Integrated Circuit")
      (fields (field (name "MOUSER PART NUMBER") "595-SN74LVC1G3157DBV"))
      (libsource (lib "SamacSys") (part "SN74LVC1G3157DBVR"))
    )
    (comp (ref "U6")
      (value "SN74LVC1G3157DBVR")
      (footprint "SamacSys:SOT95P280X145-6N")
      (description "Integrated Circuit")
      (fields (field (name "MOUSER PART NUMBER") "595-SN74LVC1G3157DBV"))
      (libsource (lib "") (part "SN74LVC1G3157DBVR_1"))
    )
    (comp (ref "U7")
      (value "AX88279")
      (footprint "IC_AX88279")
      (libsource (lib "LotusSound") (part "IC_AX88279"))
    )
    (comp (ref "U8")
      (value "ESD7016MUTAG")
      (footprint "ONSC-UDFN-8-517CB_V")
      (description "Low Capacitance ESD Protection USB 3.0, 8-Pin UDFN, Pb-Free, Tape and Reel")
      (fields (field (name "MANUFACTURER") "On Semiconductor"))
      (libsource (lib "Altium Content Vault") (part "ONSC-ESD7016-UDFN-8-517CB"))
    )
    (comp (ref "U9")
      (value "ST1S06PU33R")
      (footprint "DFN6D_L")
      (fields (field (name "MANUFACTURER") "STMicroelectronics"))
      (libsource (lib "Altium Content Vault") (part "PM-DCDC-ST1S06-IL7"))
    )
    (comp (ref "U10")
      (value "SST25VF016B-50-4I-QAF-T")
      (footprint "FP-C04-452-MFG")
      (libsource (lib "Altium Content Vault") (part "d7313dde12fd16fde488169701056cc"))
    )
    (comp (ref "U11")
      (value "ST1S06PUR")
      (footprint "DFN6D_M")
      (libsource (lib "Altium Content Vault") (part "PM-DCDC-ST1S06-IL7"))
    )
    (comp (ref "Y1")
      (value "25 MHz")
      (footprint "NDK NX3225GA")
      (description "CRYSTAL 25.0000MHZ 8PF SMD")
      (fields
        (field (name "MANUFACTURER") "NDK America, Inc.")
        (field (name "PART NUMBER") "NX3225GA-25.000M-STD-CRG-2")
      )
      (libsource (lib "Celestial Altium Library - altium_library") (part "NDK Crystal NX3225GA"))
    )
  )
  (nets
    (net (code "1") (name "/1PPS_IN") (class "Default")
      (node (ref "R11") (pin "1") (pinfunction "1_1") (pintype "passive"))
      (node (ref "U4") (pin "2") (pinfunction "A1_2") (pintype "passive"))
      (node (ref "U4") (pin "5") (pinfunction "A2_5") (pintype "passive"))
      (node (ref "U6") (pin "4") (pinfunction "A_4") (pintype "passive"))
    )
    (net (code "2") (name "/1PPS_IN_BUFF") (class "Default")
      (node (ref "R11") (pin "2") (pinfunction "2_2") (pintype "passive"))
      (node (ref "U2") (pin "3") (pinfunction "B1_3") (pintype "passive"))
      (node (ref "U4") (pin "3") (pinfunction "Y2_3") (pintype "passive"))
    )
    (net (code "3") (name "/1PPS_IN_LED") (class "Default")
      (node (ref "D2") (pin "1") (pinfunction "C_1") (pintype "passive"))
      (node (ref "U4") (pin "6") (pinfunction "Y1_6") (pintype "passive"))
    )
    (net (code "4") (name "/1PPS_OUT") (class "Default")
      (node (ref "R7") (pin "2") (pinfunction "2_2") (pintype "passive"))
      (node (ref "U1") (pin "2") (pinfunction "A1_2") (pintype "passive"))
      (node (ref "U1") (pin "5") (pinfunction "A2_5") (pintype "passive"))
      (node (ref "U2") (pin "1") (pinfunction "B2_1") (pintype "passive"))
    )
    (net (code "5") (name "/1PPS_OUT_BUFF") (class "Default")
      (node (ref "R7") (pin "1") (pinfunction "1_1") (pintype "passive"))
      (node (ref "U1") (pin "3") (pinfunction "Y2_3") (pintype "passive"))
      (node (ref "U3") (pin "1") (pinfunction "B2_1") (pintype "passive"))
    )
    (net (code "6") (name "/1PPS_OUT_LED") (class "Default")
      (node (ref "D1") (pin "1") (pinfunction "C_1") (pintype "passive"))
      (node (ref "U1") (pin "6") (pinfunction "Y1_6") (pintype "passive"))
    )
    (net (code "7") (name "/1PPS_SMA_IO") (class "Default")
      (node (ref "J1") (pin "1") (pinfunction "1_1") (pintype "passive"))
      (node (ref "U3") (pin "4") (pinfunction "A_4") (pintype "passive"))
      (node (ref "U5") (pin "1") (pinfunction "B2_1") (pintype "passive"))
    )
    (net (code "8") (name "/279_1PPS_IO") (class "Default")
      (node (ref "U2") (pin "4") (pinfunction "A_4") (pintype "passive"))
      (node (ref "U7") (pin "46") (pinfunction "GPIO14(1588_PSS)_46") (pintype "passive"))
    )
    (net (code "9") (name "/279_TOD_IN") (class "Default")
      (node (ref "IC1") (pin "2") (pinfunction "TXD_2") (pintype "passive"))
      (node (ref "IC2") (pin "20") (pinfunction "TXD_/_SPI_MISO_20") (pintype "passive"))
      (node (ref "J3") (pin "3") (pinfunction "3_3") (pintype "passive"))
      (node (ref "R24") (pin "1") (pinfunction "1_1") (pintype "passive"))
    )
    (net (code "10") (name "/279_TOD_IN_R") (class "Default")
      (node (ref "R24") (pin "2") (pinfunction "2_2") (pintype "passive"))
      (node (ref "U7") (pin "20") (pinfunction "GPIO6_20") (pintype "passive"))
    )
    (net (code "11") (name "/279_TOD_OUT") (class "Default")
      (node (ref "IC1") (pin "3") (pinfunction "RXD_3") (pintype "passive"))
      (node (ref "IC2") (pin "21") (pinfunction "RXD_/_SPI_MOSI_21") (pintype "passive"))
      (node (ref "J3") (pin "4") (pinfunction "4_4") (pintype "passive"))
      (node (ref "R25") (pin "1") (pinfunction "1_1") (pintype "passive"))
    )
    (net (code "12") (name "/279_TOD_OUT_R") (class "Default")
      (node (ref "R25") (pin "2") (pinfunction "2_2") (pintype "passive"))
      (node (ref "U7") (pin "21") (pinfunction "GPIO7_21") (pintype "passive"))
    )
    (net (code "13") (name "/ANT") (class "Default")
      (node (ref "FB5") (pin "2") (pinfunction "2_2") (pintype "passive"))
      (node (ref "IC1") (pin "11") (pinfunction "RF_IN_11") (pintype "passive"))
      (node (ref "IC2") (pin "11") (pinfunction "RF_IN_11") (pintype "passive"))
      (node (ref "J2") (pin "1") (pinfunction "1_1") (pintype "passive"))
    )
    (net (code "14") (name "/AVDD10") (class "Default")
      (node (ref "C13") (pin "2") (pinfunction "2_2") (pintype "passive"))
      (node (ref "C14") (pin "2") (pinfunction "2_2") (pintype "passive"))
      (node (ref "FB1") (pin "2") (pinfunction "2_2") (pintype "passive"))
      (node (ref "U7") (pin "43") (pinfunction "AVDD10_SSUSB_43") (pintype "passive"))
    )
    (net (code "15") (name "/AVDD_1.85") (class "Default")
      (node (ref "C36") (pin "2") (pinfunction "2_2") (pintype "passive"))
      (node (ref "C37") (pin "2") (pinfunction "2_2") (pintype "passive"))
      (node (ref "FB2") (pin "2") (pinfunction "2_2") (pintype "passive"))
      (node (ref "FB4") (pin "2") (pinfunction "2_2") (pintype "passive"))
      (node (ref "U7") (pin "40") (pinfunction "AVDD18_SSUSB_40") (pintype "passive"))
      (node (ref "U7") (pin "8") (pinfunction "AVDD18_COM_8") (pintype "passive"))
    )
    (net (code "16") (name "/AVDD_33") (class "Default")
      (node (ref "C26") (pin "2") (pinfunction "2_2") (pintype "passive"))
      (node (ref "C27") (pin "2") (pinfunction "2_2") (pintype "passive"))
      (node (ref "C28") (pin "2") (pinfunction "2_2") (pintype "passive"))
      (node (ref "C29") (pin "2") (pinfunction "2_2") (pintype "passive"))
      (node (ref "C30") (pin "2") (pinfunction "2_2") (pintype "passive"))
      (node (ref "FB3") (pin "2") (pinfunction "2_2") (pintype "passive"))
      (node (ref "U7") (pin "12") (pinfunction "AVDD33_LD_12") (pintype "passive"))
      (node (ref "U7") (pin "37") (pinfunction "GPIO13/AVD33_USB_37") (pintype "passive"))
      (node (ref "U7") (pin "5") (pinfunction "AVD33_LD_5") (pintype "passive"))
    )
    (net (code "17") (name "/DVDD_1.85") (class "Default")
      (node (ref "C19") (pin "2") (pinfunction "2_2") (pintype "passive"))
      (node (ref "C33") (pin "2") (pinfunction "2_2") (pintype "passive"))
      (node (ref "C34") (pin "2") (pinfunction "2_2") (pintype "passive"))
      (node (ref "C35") (pin "2") (pinfunction "2_2") (pintype "passive"))
      (node (ref "FB4") (pin "1") (pinfunction "1_1") (pintype "passive"))
      (node (ref "U7") (pin "26") (pinfunction "DVDD18_26") (pintype "passive"))
      (node (ref "U7") (pin "35") (pinfunction "DVDD18_35") (pintype "passive"))
      (node (ref "U7") (pin "53") (pinfunction "DVDD18_53") (pintype "passive"))
      (node (ref "U7") (pin "56") (pinfunction "LDO18_56") (pintype "passive"))
    )
    (net (code "18") (name "/D_N") (class "Default")
      (node (ref "J5") (pin "A7") (pinfunction "Dn1_A7") (pintype "passive"))
      (node (ref "J5") (pin "B7") (pinfunction "Dn2_B7") (pintype "passive"))
      (node (ref "U7") (pin "38") (pinfunction "GPIO12_USB_DN_38") (pintype "passive"))
      (node (ref "U8") (pin "5") (pinfunction "I/O_5") (pintype "passive"))
    )
    (net (code "19") (name "/D_P") (class "Default")
      (node (ref "J5") (pin "A6") (pinfunction "Dp1_A6") (pintype "passive"))
      (node (ref "J5") (pin "B6") (pinfunction "Dp2_B6") (pintype "passive"))
      (node (ref "U7") (pin "39") (pinfunction "GPIO12_USB_DP_39") (pintype "passive"))
      (node (ref "U8") (pin "4") (pinfunction "I/O_4") (pintype "passive"))
    )
    (net (code "20") (name "/GPS_PPS_OUT") (class "Default")
      (node (ref "IC1") (pin "4") (pinfunction "TIMEPULSE_4") (pintype "passive"))
      (node (ref "IC2") (pin "3") (pinfunction "TIMEPULSE_3") (pintype "passive"))
      (node (ref "J3") (pin "5") (pinfunction "5_5") (pintype "passive"))
      (node (ref "U5") (pin "4") (pinfunction "A_4") (pintype "passive"))
    )
    (net (code "21") (name "/LED0") (class "Default")
      (node (ref "J4") (pin "P12") (pinfunction "K_GREEN_P12") (pintype "passive"))
      (node (ref "R18") (pin "2") (pinfunction "2_2") (pintype "passive"))
      (node (ref "U7") (pin "27") (pinfunction "GPIO5(LED0)_27") (pintype "passive"))
    )
    (net (code "22") (name "/LED1") (class "Default")
      (node (ref "J4") (pin "P14") (pinfunction "K_YELLOW_P14") (pintype "passive"))
      (node (ref "R19") (pin "2") (pinfunction "2_2") (pintype "passive"))
      (node (ref "U7") (pin "28") (pinfunction "GPIO4(LED1)_28") (pintype "passive"))
    )
    (net (code "23") (name "/MDI0_N") (class "Default")
      (node (ref "J4") (pin "P2") (pinfunction "TD1-_P2") (pintype "passive"))
      (node (ref "U7") (pin "4") (pinfunction "TXVN_A_4") (pintype "passive"))
    )
    (net (code "24") (name "/MDI0_P") (class "Default")
      (node (ref "J4") (pin "P1") (pinfunction "TD1+_P1") (pintype "passive"))
      (node (ref "U7") (pin "3") (pinfunction "TXVP_A_3") (pintype "passive"))
    )
    (net (code "25") (name "/MDI1_N") (class "Default")
      (node (ref "J4") (pin "P4") (pinfunction "TD2-_P4") (pintype "passive"))
      (node (ref "U7") (pin "7") (pinfunction "TXVP_B_7") (pintype "passive"))
    )
    (net (code "26") (name "/MDI1_P") (class "Default")
      (node (ref "J4") (pin "P3") (pinfunction "TD2+_P3") (pintype "passive"))
      (node (ref "U7") (pin "6") (pinfunction "TXVP_B_6") (pintype "passive"))
    )
    (net (code "27") (name "/MDI2_N") (class "Default")
      (node (ref "J4") (pin "P6") (pinfunction "TD3-_P6") (pintype "passive"))
      (node (ref "U7") (pin "11") (pinfunction "TXVN_C_11") (pintype "passive"))
    )
    (net (code "28") (name "/MDI2_P") (class "Default")
      (node (ref "J4") (pin "P5") (pinfunction "TD3+_P5") (pintype "passive"))
      (node (ref "U7") (pin "10") (pinfunction "TXVP_C_10") (pintype "passive"))
    )
    (net (code "29") (name "/MDI3_N") (class "Default")
      (node (ref "J4") (pin "P8") (pinfunction "TD4-_P8") (pintype "passive"))
      (node (ref "U7") (pin "14") (pinfunction "TXVN_D_14") (pintype "passive"))
    )
    (net (code "30") (name "/MDI3_P") (class "Default")
      (node (ref "J4") (pin "P7") (pinfunction "TD4+_P7") (pintype "passive"))
      (node (ref "U7") (pin "13") (pinfunction "TXVP_D_13") (pintype "passive"))
    )
    (net (code "31") (name "/MUX1_CTRL") (class "Default")
      (node (ref "R3") (pin "1") (pinfunction "1_1") (pintype "passive"))
      (node (ref "SW1") (pin "8") (pinfunction "8_8") (pintype "passive"))
      (node (ref "U3") (pin "6") (pinfunction "S_6") (pintype "passive"))
    )
    (net (code "32") (name "/MUX2_CTRL") (class "Default")
      (node (ref "R4") (pin "1") (pinfunction "1_1") (pintype "passive"))
      (node (ref "SW1") (pin "7") (pinfunction "7_7") (pintype "passive"))
      (node (ref "U2") (pin "6") (pinfunction "S_6") (pintype "passive"))
    )
    (net (code "33") (name "/MUX3_CTRL") (class "Default")
      (node (ref "R5") (pin "1") (pinfunction "1_1") (pintype "passive"))
      (node (ref "SW1") (pin "6") (pinfunction "6_6") (pintype "passive"))
      (node (ref "U6") (pin "6") (pinfunction "S_6") (pintype "passive"))
    )
    (net (code "34") (name "/MUX4_CTRL") (class "Default")
      (node (ref "R6") (pin "1") (pinfunction "1_1") (pintype "passive"))
      (node (ref "SW1") (pin "5") (pinfunction "5_5") (pintype "passive"))
      (node (ref "U5") (pin "6") (pinfunction "S_6") (pintype "passive"))
    )
    (net (code "35") (name "/RESET_N") (class "Default")
      (node (ref "R16") (pin "1") (pinfunction "1_1") (pintype "passive"))
      (node (ref "U7") (pin "23") (pinfunction "HW_RSTN_23") (pintype "passive"))
    )
    (net (code "36") (name "/SB") (class "Default")
      (node (ref "IC1") (pin "18") (pinfunction "SAFEBOOT_N_18") (pintype "passive"))
      (node (ref "IC2") (pin "1") (pinfunction "SAFEBOOT_N_1") (pintype "passive"))
      (node (ref "R14") (pin "1") (pinfunction "1_1") (pintype "passive"))
    )
    (net (code "37") (name "/SCL") (class "Default")
      (node (ref "IC1") (pin "17") (pinfunction "SCL_17") (pintype "passive"))
      (node (ref "IC2") (pin "19") (pinfunction "SCL_/_SPI_SLK__19") (pintype "passive"))
      (node (ref "TP2") (pin "1") (pinfunction "1_1") (pintype "passive"))
    )
    (net (code "38") (name "/SDA") (class "Default")
      (node (ref "IC1") (pin "16") (pinfunction "SDA_16") (pintype "passive"))
      (node (ref "IC2") (pin "18") (pinfunction "SDA_/_SPI_CS_N_18") (pintype "passive"))
      (node (ref "TP1") (pin "1") (pinfunction "1_1") (pintype "passive"))
    )
    (net (code "39") (name "/SPI_CLK") (class "Default")
      (node (ref "R32") (pin "2") (pinfunction "2_2") (pintype "passive"))
      (node (ref "U10") (pin "6") (pinfunction "SCK_6") (pintype "input"))
      (node (ref "U7") (pin "51") (pinfunction "SPI_CLK_51") (pintype "passive"))
    )
    (net (code "40") (name "/SPI_CS") (class "Default")
      (node (ref "U10") (pin "1") (pinfunction "~{CE}_1") (pintype "input"))
      (node (ref "U7") (pin "50") (pinfunction "SPI_CS0_50") (pintype "passive"))
    )
    (net (code "41") (name "/SPI_DIO") (class "Default")
      (node (ref "R31") (pin "2") (pinfunction "2_2") (pintype "passive"))
      (node (ref "R35") (pin "2") (pinfunction "2_2") (pintype "passive"))
      (node (ref "U10") (pin "5") (pinfunction "SI_5") (pintype "input"))
      (node (ref "U7") (pin "52") (pinfunction "SPI_DIO_52") (pintype "passive"))
    )
    (net (code "42") (name "/SSRX_N") (class "Default")
      (node (ref "J5") (pin "A10") (pinfunction "SSRXn2_A10") (pintype "passive"))
      (node (ref "J5") (pin "B10") (pinfunction "SSRXn1_B10") (pintype "passive"))
      (node (ref "U7") (pin "44") (pinfunction "SSUSBRXN_44") (pintype "passive"))
      (node (ref "U8") (pin "7") (pinfunction "I/O_7") (pintype "passive"))
    )
    (net (code "43") (name "/SSRX_P") (class "Default")
      (node (ref "J5") (pin "A11") (pinfunction "SSRXp2_A11") (pintype "passive"))
      (node (ref "J5") (pin "B11") (pinfunction "SSRXp1_B11") (pintype "passive"))
      (node (ref "U7") (pin "45") (pinfunction "SSUSBRXP_45") (pintype "passive"))
      (node (ref "U8") (pin "8") (pinfunction "I/O_8") (pintype "passive"))
    )
    (net (code "44") (name "/SSTX_N") (class "Default")
      (node (ref "C9") (pin "2") (pinfunction "2_2") (pintype "passive"))
      (node (ref "U7") (pin "41") (pinfunction "SSUSB_TXN_41") (pintype "passive"))
    )
    (net (code "45") (name "/SSTX_P") (class "Default")
      (node (ref "C8") (pin "2") (pinfunction "2_2") (pintype "passive"))
      (node (ref "U7") (pin "42") (pinfunction "SSUSB_TXP_42") (pintype "passive"))
    )
    (net (code "46") (name "/USB3.0_SSTX_N") (class "Default")
      (node (ref "C9") (pin "1") (pinfunction "1_1") (pintype "passive"))
      (node (ref "J5") (pin "A3") (pinfunction "SSTXn1_A3") (pintype "passive"))
      (node (ref "J5") (pin "B3") (pinfunction "SSTXn2_B3") (pintype "passive"))
      (node (ref "U8") (pin "1") (pinfunction "I/O_1") (pintype "passive"))
    )
    (net (code "47") (name "/USB3.0_SSTX_P") (class "Default")
      (node (ref "C8") (pin "1") (pinfunction "1_1") (pintype "passive"))
      (node (ref "J5") (pin "A2") (pinfunction "SSTXp1_A2") (pintype "passive"))
      (node (ref "J5") (pin "B2") (pinfunction "SSTXp2_B2") (pintype "passive"))
      (node (ref "U8") (pin "2") (pinfunction "I/O_2") (pintype "passive"))
    )
    (net (code "48") (name "/VBUS") (class "Default")
      (node (ref "R15") (pin "1") (pinfunction "1_1") (pintype "passive"))
      (node (ref "R17") (pin "2") (pinfunction "2_2") (pintype "passive"))
      (node (ref "U7") (pin "34") (pinfunction "GPIO9(VBUS)_34") (pintype "passive"))
    )
    (net (code "49") (name "/VCC_RF") (class "Default")
      (node (ref "IC1") (pin "14") (pinfunction "VCC_RF_14") (pintype "passive"))
      (node (ref "IC2") (pin "9") (pinfunction "VCC_RF_9") (pintype "passive"))
      (node (ref "R38") (pin "1") (pinfunction "1_1") (pintype "passive"))
    )
    (net (code "50") (name "/VCORE_LDO") (class "Default")
      (node (ref "C18") (pin "2") (pinfunction "2_2") (pintype "passive"))
      (node (ref "FB1") (pin "1") (pinfunction "1_1") (pintype "passive"))
      (node (ref "U7") (pin "55") (pinfunction "VCORE_LDO_55") (pintype "passive"))
    )
    (net (code "51") (name "/XTL20N") (class "Default")
      (node (ref "R27") (pin "2") (pinfunction "2_2") (pintype "passive"))
      (node (ref "U7") (pin "16") (pinfunction "XTAL_XO_16") (pintype "passive"))
    )
    (net (code "52") (name "/XTL20P") (class "Default")
      (node (ref "R26") (pin "2") (pinfunction "2_2") (pintype "passive"))
      (node (ref "U7") (pin "17") (pinfunction "XTAL_IN_17") (pintype "passive"))
    )
    (net (code "53") (name "CHASSIS_GND") (class "Default")
      (node (ref "C7") (pin "1") (pinfunction "1_1") (pintype "passive"))
      (node (ref "J4") (pin "MH1") (pinfunction "MH1_MH1") (pintype "passive"))
      (node (ref "J4") (pin "MH2") (pinfunction "MH2_MH2") (pintype "passive"))
      (node (ref "R13") (pin "1") (pinfunction "1_1") (pintype "passive"))
    )
    (net (code "54") (name "DVDD_33") (class "Default")
      (node (ref "C15") (pin "2") (pinfunction "2_2") (pintype "passive"))
      (node (ref "C16") (pin "2") (pinfunction "2_2") (pintype "passive"))
      (node (ref "C22") (pin "2") (pinfunction "2_2") (pintype "passive"))
      (node (ref "C23") (pin "2") (pinfunction "2_2") (pintype "passive"))
      (node (ref "C24") (pin "2") (pinfunction "2_2") (pintype "passive"))
      (node (ref "C25") (pin "2") (pinfunction "2_2") (pintype "passive"))
      (node (ref "C43") (pin "2") (pinfunction "2_2") (pintype "passive"))
      (node (ref "C44") (pin "2") (pinfunction "2_2") (pintype "passive"))
      (node (ref "FB3") (pin "1") (pinfunction "1_1") (pintype "passive"))
      (node (ref "IC1") (pin "7") (pinfunction "V_IO_7") (pintype "passive"))
      (node (ref "IC1") (pin "8") (pinfunction "VCC_8") (pintype "passive"))
      (node (ref "IC2") (pin "2") (pinfunction "D_SEL_2") (pintype "passive"))
      (node (ref "IC2") (pin "23") (pinfunction "VCC_23") (pintype "passive"))
      (node (ref "IC2") (pin "7") (pinfunction "V_USB_7") (pintype "passive"))
      (node (ref "L1") (pin "2") (pinfunction "2_2") (pintype "passive"))
      (node (ref "R10") (pin "2") (pinfunction "2_2") (pintype "passive"))
      (node (ref "R12") (pin "2") (pinfunction "2_2") (pintype "passive"))
      (node (ref "R16") (pin "2") (pinfunction "2_2") (pintype "passive"))
      (node (ref "R18") (pin "1") (pinfunction "1_1") (pintype "passive"))
      (node (ref "R19") (pin "1") (pinfunction "1_1") (pintype "passive"))
      (node (ref "R21") (pin "2") (pinfunction "2_2") (pintype "passive"))
      (node (ref "R22") (pin "2") (pinfunction "2_2") (pintype "passive"))
      (node (ref "R23") (pin "2") (pinfunction "2_2") (pintype "passive"))
      (node (ref "R31") (pin "1") (pinfunction "1_1") (pintype "passive"))
      (node (ref "R32") (pin "1") (pinfunction "1_1") (pintype "passive"))
      (node (ref "R33") (pin "1") (pinfunction "1_1") (pintype "passive"))
      (node (ref "R34") (pin "1") (pinfunction "1_1") (pintype "passive"))
      (node (ref "U10") (pin "8") (pinfunction "VDD_8") (pintype "power_in"))
      (node (ref "U7") (pin "25") (pinfunction "DVDD33_25") (pintype "passive"))
      (node (ref "U7") (pin "36") (pinfunction "DVDD33_36") (pintype "passive"))
      (node (ref "U7") (pin "54") (pinfunction "AVDD33_LDO_54") (pintype "passive"))
      (node (ref "U7") (pin "59") (pinfunction "AVD33_BUCK_59") (pintype "passive"))
      (node (ref "U9") (pin "1") (pinfunction "VO/VFB_1") (pintype "bidirectional"))
    )
    (net (code "55") (name "GND") (class "Default")
      (node (ref "C1") (pin "1") (pinfunction "1_1") (pintype "passive"))
      (node (ref "C10") (pin "1") (pinfunction "1_1") (pintype "passive"))
      (node (ref "C11") (pin "1") (pinfunction "1_1") (pintype "passive"))
      (node (ref "C12") (pin "1") (pinfunction "1_1") (pintype "passive"))
      (node (ref "C13") (pin "1") (pinfunction "1_1") (pintype "passive"))
      (node (ref "C14") (pin "1") (pinfunction "1_1") (pintype "passive"))
      (node (ref "C15") (pin "1") (pinfunction "1_1") (pintype "passive"))
      (node (ref "C16") (pin "1") (pinfunction "1_1") (pintype "passive"))
      (node (ref "C17") (pin "1") (pinfunction "1_1") (pintype "passive"))
      (node (ref "C18") (pin "1") (pinfunction "1_1") (pintype "passive"))
      (node (ref "C19") (pin "1") (pinfunction "1_1") (pintype "passive"))
      (node (ref "C2") (pin "1") (pinfunction "1_1") (pintype "passive"))
      (node (ref "C20") (pin "1") (pinfunction "1_1") (pintype "passive"))
      (node (ref "C21") (pin "1") (pinfunction "1_1") (pintype "passive"))
      (node (ref "C22") (pin "1") (pinfunction "1_1") (pintype "passive"))
      (node (ref "C23") (pin "1") (pinfunction "1_1") (pintype "passive"))
      (node (ref "C24") (pin "1") (pinfunction "1_1") (pintype "passive"))
      (node (ref "C25") (pin "1") (pinfunction "1_1") (pintype "passive"))
      (node (ref "C26") (pin "1") (pinfunction "1_1") (pintype "passive"))
      (node (ref "C27") (pin "1") (pinfunction "1_1") (pintype "passive"))
      (node (ref "C28") (pin "1") (pinfunction "1_1") (pintype "passive"))
      (node (ref "C29") (pin "1") (pinfunction "1_1") (pintype "passive"))
      (node (ref "C3") (pin "1") (pinfunction "1_1") (pintype "passive"))
      (node (ref "C30") (pin "1") (pinfunction "1_1") (pintype "passive"))
      (node (ref "C31") (pin "1") (pinfunction "1_1") (pintype "passive"))
      (node (ref "C32") (pin "1") (pinfunction "1_1") (pintype "passive"))
      (node (ref "C33") (pin "1") (pinfunction "1_1") (pintype "passive"))
      (node (ref "C34") (pin "1") (pinfunction "1_1") (pintype "passive"))
      (node (ref "C35") (pin "1") (pinfunction "1_1") (pintype "passive"))
      (node (ref "C36") (pin "1") (pinfunction "1_1") (pintype "passive"))
      (node (ref "C37") (pin "1") (pinfunction "1_1") (pintype "passive"))
      (node (ref "C38") (pin "1") (pinfunction "1_1") (pintype "passive"))
      (node (ref "C39") (pin "1") (pinfunction "1_1") (pintype "passive"))
      (node (ref "C4") (pin "1") (pinfunction "1_1") (pintype "passive"))
      (node (ref "C40") (pin "1") (pinfunction "1_1") (pintype "passive"))
      (node (ref "C41") (pin "1") (pinfunction "1_1") (pintype "passive"))
      (node (ref "C42") (pin "1") (pinfunction "1_1") (pintype "passive"))
      (node (ref "C43") (pin "1") (pinfunction "1_1") (pintype "passive"))
      (node (ref "C44") (pin "1") (pinfunction "1_1") (pintype "passive"))
      (node (ref "C5") (pin "1") (pinfunction "1_1") (pintype "passive"))
      (node (ref "C6") (pin "1") (pinfunction "1_1") (pintype "passive"))
      (node (ref "C7") (pin "2") (pinfunction "2_2") (pintype "passive"))
      (node (ref "IC1") (pin "1") (pinfunction "GND_1_1") (pintype "passive"))
      (node (ref "IC1") (pin "10") (pinfunction "GND_2_10") (pintype "passive"))
      (node (ref "IC1") (pin "12") (pinfunction "GND_3_12") (pintype "passive"))
      (node (ref "IC2") (pin "10") (pinfunction "GND_1_10") (pintype "passive"))
      (node (ref "IC2") (pin "12") (pinfunction "GND_2_12") (pintype "passive"))
      (node (ref "IC2") (pin "13") (pinfunction "GND_3_13") (pintype "passive"))
      (node (ref "IC2") (pin "24") (pinfunction "GND_4_24") (pintype "passive"))
      (node (ref "J1") (pin "2") (pinfunction "2_2") (pintype "passive"))
      (node (ref "J1") (pin "3") (pinfunction "3_3") (pintype "passive"))
      (node (ref "J1") (pin "4") (pinfunction "4_4") (pintype "passive"))
      (node (ref "J1") (pin "5") (pinfunction "5_5") (pintype "passive"))
      (node (ref "J2") (pin "2") (pinfunction "2_2") (pintype "passive"))
      (node (ref "J2") (pin "3") (pinfunction "3_3") (pintype "passive"))
      (node (ref "J2") (pin "4") (pinfunction "4_4") (pintype "passive"))
      (node (ref "J2") (pin "5") (pinfunction "5_5") (pintype "passive"))
      (node (ref "J3") (pin "1") (pinfunction "1_1") (pintype "passive"))
      (node (ref "J4") (pin "P10") (pinfunction "GND_P10") (pintype "passive"))
      (node (ref "J5") (pin "A1") (pinfunction "GND_A1") (pintype "passive"))
      (node (ref "J5") (pin "A12") (pinfunction "GND_A12") (pintype "passive"))
      (node (ref "J5") (pin "B1") (pinfunction "GND_B1") (pintype "passive"))
      (node (ref "J5") (pin "B12") (pinfunction "GND_B12") (pintype "passive"))
      (node (ref "R1") (pin "2") (pinfunction "2_2") (pintype "passive"))
      (node (ref "R13") (pin "2") (pinfunction "2_2") (pintype "passive"))
      (node (ref "R14") (pin "2") (pinfunction "2_2") (pintype "passive"))
      (node (ref "R17") (pin "1") (pinfunction "1_1") (pintype "passive"))
      (node (ref "R20") (pin "1") (pinfunction "1_1") (pintype "passive"))
      (node (ref "R28") (pin "2") (pinfunction "2_2") (pintype "passive"))
      (node (ref "R29") (pin "1") (pinfunction "1_1") (pintype "passive"))
      (node (ref "R30") (pin "2") (pinfunction "2_2") (pintype "passive"))
      (node (ref "R37") (pin "2") (pinfunction "2_2") (pintype "passive"))
      (node (ref "R8") (pin "1") (pinfunction "1_1") (pintype "passive"))
      (node (ref "SW1") (pin "1") (pinfunction "GND_1") (pintype "passive"))
      (node (ref "SW1") (pin "2") (pinfunction "GND_2") (pintype "passive"))
      (node (ref "SW1") (pin "3") (pinfunction "GND_3") (pintype "passive"))
      (node (ref "SW1") (pin "4") (pinfunction "GND_4") (pintype "passive"))
      (node (ref "U1") (pin "4") (pinfunction "GND_4") (pintype "passive"))
      (node (ref "U10") (pin "4") (pinfunction "VSS_4") (pintype "power_in"))
      (node (ref "U10") (pin "9") (pinfunction "VSS_9") (pintype "power_in"))
      (node (ref "U11") (pin "2") (pinfunction "GND_2") (pintype "power_in"))
      (node (ref "U11") (pin "7") (pinfunction "Thermal_Pad_7") (pintype "power_in"))
      (node (ref "U2") (pin "2") (pinfunction "GND_2") (pintype "passive"))
      (node (ref "U3") (pin "2") (pinfunction "GND_2") (pintype "passive"))
      (node (ref "U4") (pin "4") (pinfunction "GND_4") (pintype "passive"))
      (node (ref "U5") (pin "2") (pinfunction "GND_2") (pintype "passive"))
      (node (ref "U6") (pin "2") (pinfunction "GND_2") (pintype "passive"))
      (node (ref "U7") (pin "1") (pinfunction "AVSS33_BUCK_1") (pintype "passive"))
      (node (ref "U7") (pin "2") (pinfunction "AVSS33_BUCK_2") (pintype "passive"))
      (node (ref "U7") (pin "61") (pinfunction "E_PAD_61") (pintype "passive"))
      (node (ref "U8") (pin "6") (pinfunction "GND_6") (pintype "power_in"))
      (node (ref "U9") (pin "2") (pinfunction "GND_2") (pintype "power_in"))
      (node (ref "U9") (pin "7") (pinfunction "Thermal_Pad_7") (pintype "power_in"))
      (node (ref "Y1") (pin "2") (pinfunction "GND_2") (pintype "passive"))
      (node (ref "Y1") (pin "4") (pinfunction "GND_4") (pintype "passive"))
    )
    (net (code "56") (name "Net-(C10-Pad2)") (class "Default")
      (node (ref "C10") (pin "2") (pinfunction "2_2") (pintype "passive"))
      (node (ref "R26") (pin "1") (pinfunction "1_1") (pintype "passive"))
      (node (ref "Y1") (pin "1") (pinfunction "1_1") (pintype "passive"))
    )
    (net (code "57") (name "Net-(C11-Pad2)") (class "Default")
      (node (ref "C11") (pin "2") (pinfunction "2_2") (pintype "passive"))
      (node (ref "R27") (pin "1") (pinfunction "1_1") (pintype "passive"))
      (node (ref "Y1") (pin "3") (pinfunction "3_3") (pintype "passive"))
    )
    (net (code "58") (name "Net-(C42-Pad2)") (class "Default")
      (node (ref "C42") (pin "2") (pinfunction "2_2") (pintype "passive"))
      (node (ref "FB5") (pin "1") (pinfunction "1_1") (pintype "passive"))
      (node (ref "R38") (pin "2") (pinfunction "2_2") (pintype "passive"))
    )
    (net (code "59") (name "Net-(D1-A)") (class "Default")
      (node (ref "D1") (pin "2") (pinfunction "A_2") (pintype "passive"))
      (node (ref "R2") (pin "1") (pinfunction "1_1") (pintype "passive"))
    )
    (net (code "60") (name "Net-(D2-A)") (class "Default")
      (node (ref "D2") (pin "2") (pinfunction "A_2") (pintype "passive"))
      (node (ref "R9") (pin "1") (pinfunction "1_1") (pintype "passive"))
    )
    (net (code "61") (name "Net-(J4-A_GREEN)") (class "Default")
      (node (ref "J4") (pin "P11") (pinfunction "A_GREEN_P11") (pintype "passive"))
      (node (ref "R10") (pin "1") (pinfunction "1_1") (pintype "passive"))
    )
    (net (code "62") (name "Net-(J4-A_YELLOW)") (class "Default")
      (node (ref "J4") (pin "P13") (pinfunction "A_YELLOW_P13") (pintype "passive"))
      (node (ref "R12") (pin "1") (pinfunction "1_1") (pintype "passive"))
    )
    (net (code "63") (name "Net-(J5-CC1)") (class "Default")
      (node (ref "J5") (pin "A5") (pinfunction "CC1_A5") (pintype "passive"))
      (node (ref "R28") (pin "1") (pinfunction "1_1") (pintype "passive"))
    )
    (net (code "64") (name "Net-(J5-CC2)") (class "Default")
      (node (ref "J5") (pin "B5") (pinfunction "CC2_B5") (pintype "passive"))
      (node (ref "R30") (pin "1") (pinfunction "1_1") (pintype "passive"))
    )
    (net (code "65") (name "Net-(J5-Shield)") (class "Default")
      (node (ref "C12") (pin "2") (pinfunction "2_2") (pintype "passive"))
      (node (ref "J5") (pin "S") (pinfunction "Shield_S") (pintype "passive"))
      (node (ref "R29") (pin "2") (pinfunction "2_2") (pintype "passive"))
    )
    (net (code "66") (name "Net-(U1-~{OE1})") (class "Default")
      (node (ref "R1") (pin "1") (pinfunction "1_1") (pintype "passive"))
      (node (ref "U1") (pin "1") (pinfunction "~{OE1}_1") (pintype "passive"))
      (node (ref "U1") (pin "7") (pinfunction "~{OE2}_7") (pintype "passive"))
    )
    (net (code "67") (name "Net-(U3-B1)") (class "Default")
      (node (ref "U3") (pin "3") (pinfunction "B1_3") (pintype "passive"))
      (node (ref "U6") (pin "1") (pinfunction "B2_1") (pintype "passive"))
    )
    (net (code "68") (name "Net-(U4-~{OE1})") (class "Default")
      (node (ref "R8") (pin "2") (pinfunction "2_2") (pintype "passive"))
      (node (ref "U4") (pin "1") (pinfunction "~{OE1}_1") (pintype "passive"))
      (node (ref "U4") (pin "7") (pinfunction "~{OE2}_7") (pintype "passive"))
    )
    (net (code "69") (name "Net-(U5-B1)") (class "Default")
      (node (ref "U5") (pin "3") (pinfunction "B1_3") (pintype "passive"))
      (node (ref "U6") (pin "3") (pinfunction "B1_3") (pintype "passive"))
    )
    (net (code "70") (name "Net-(U7-AVDD18_XTAL)") (class "Default")
      (node (ref "C20") (pin "2") (pinfunction "2_2") (pintype "passive"))
      (node (ref "C21") (pin "2") (pinfunction "2_2") (pintype "passive"))
      (node (ref "FB2") (pin "1") (pinfunction "1_1") (pintype "passive"))
      (node (ref "U7") (pin "15") (pinfunction "AVDD18_XTAL_15") (pintype "passive"))
    )
    (net (code "71") (name "Net-(U7-GPIO3(LED2))") (class "Default")
      (node (ref "R21") (pin "1") (pinfunction "1_1") (pintype "passive"))
      (node (ref "U7") (pin "29") (pinfunction "GPIO3(LED2)_29") (pintype "passive"))
    )
    (net (code "72") (name "Net-(U7-GPIO8(WAKEUP_B))") (class "Default")
      (node (ref "R23") (pin "1") (pinfunction "1_1") (pintype "passive"))
      (node (ref "U7") (pin "33") (pinfunction "GPIO8(WAKEUP_B)_33") (pintype "passive"))
    )
    (net (code "73") (name "Net-(U7-GPIO10(SYNCE_LOCK))") (class "Default")
      (node (ref "R22") (pin "1") (pinfunction "1_1") (pintype "passive"))
      (node (ref "U7") (pin "19") (pinfunction "GPIO10(SYNCE_LOCK)_19") (pintype "passive"))
    )
    (net (code "74") (name "Net-(U7-MPXP)") (class "Default")
      (node (ref "R20") (pin "2") (pinfunction "2_2") (pintype "passive"))
      (node (ref "U7") (pin "9") (pinfunction "MPXP_9") (pintype "passive"))
    )
    (net (code "75") (name "Net-(U9-SW)") (class "Default")
      (node (ref "L1") (pin "1") (pinfunction "1_1") (pintype "passive"))
      (node (ref "U9") (pin "3") (pinfunction "SW_3") (pintype "passive"))
    )
    (net (code "76") (name "Net-(U10-SO)") (class "Default")
      (node (ref "R35") (pin "1") (pinfunction "1_1") (pintype "passive"))
      (node (ref "U10") (pin "2") (pinfunction "SO_2") (pintype "output"))
    )
    (net (code "77") (name "Net-(U10-~{HOLD})") (class "Default")
      (node (ref "R33") (pin "2") (pinfunction "2_2") (pintype "passive"))
      (node (ref "U10") (pin "7") (pinfunction "~{HOLD}_7") (pintype "input"))
    )
    (net (code "78") (name "Net-(U10-~{WP})") (class "Default")
      (node (ref "R34") (pin "2") (pinfunction "2_2") (pintype "passive"))
      (node (ref "U10") (pin "3") (pinfunction "~{WP}_3") (pintype "input"))
    )
    (net (code "79") (name "Net-(U11-SW)") (class "Default")
      (node (ref "L2") (pin "1") (pinfunction "1_1") (pintype "passive"))
      (node (ref "U11") (pin "3") (pinfunction "SW_3") (pintype "passive"))
    )
    (net (code "80") (name "Net-(U11-VO{slash}VFB)") (class "Default")
      (node (ref "R36") (pin "2") (pinfunction "2_2") (pintype "passive"))
      (node (ref "R37") (pin "1") (pinfunction "1_1") (pintype "passive"))
      (node (ref "U11") (pin "1") (pinfunction "VO/VFB_1") (pintype "bidirectional"))
    )
    (net (code "81") (name "VBUS_+5V") (class "Default")
      (node (ref "C1") (pin "2") (pinfunction "2_2") (pintype "passive"))
      (node (ref "C17") (pin "2") (pinfunction "2_2") (pintype "passive"))
      (node (ref "C2") (pin "2") (pinfunction "2_2") (pintype "passive"))
      (node (ref "C3") (pin "2") (pinfunction "2_2") (pintype "passive"))
      (node (ref "C32") (pin "2") (pinfunction "2_2") (pintype "passive"))
      (node (ref "C4") (pin "2") (pinfunction "2_2") (pintype "passive"))
      (node (ref "C5") (pin "2") (pinfunction "2_2") (pintype "passive"))
      (node (ref "C6") (pin "2") (pinfunction "2_2") (pintype "passive"))
      (node (ref "J3") (pin "2") (pinfunction "2_2") (pintype "passive"))
      (node (ref "J5") (pin "A4") (pinfunction "VBUS_A4") (pintype "passive"))
      (node (ref "J5") (pin "A9") (pinfunction "VBUS_A9") (pintype "passive"))
      (node (ref "J5") (pin "B4") (pinfunction "VBUS_B4") (pintype "passive"))
      (node (ref "J5") (pin "B9") (pinfunction "VBUS_B9") (pintype "passive"))
      (node (ref "R15") (pin "2") (pinfunction "2_2") (pintype "passive"))
      (node (ref "R2") (pin "2") (pinfunction "2_2") (pintype "passive"))
      (node (ref "R3") (pin "2") (pinfunction "2_2") (pintype "passive"))
      (node (ref "R4") (pin "2") (pinfunction "2_2") (pintype "passive"))
      (node (ref "R5") (pin "2") (pinfunction "2_2") (pintype "passive"))
      (node (ref "R6") (pin "2") (pinfunction "2_2") (pintype "passive"))
      (node (ref "R9") (pin "2") (pinfunction "2_2") (pintype "passive"))
      (node (ref "U1") (pin "8") (pinfunction "VCC_8") (pintype "passive"))
      (node (ref "U11") (pin "4") (pinfunction "VIN_SW_4") (pintype "input"))
      (node (ref "U11") (pin "5") (pinfunction "VIN_A_5") (pintype "input"))
      (node (ref "U11") (pin "6") (pinfunction "VINH_6") (pintype "input"))
      (node (ref "U2") (pin "5") (pinfunction "VCC_5") (pintype "passive"))
      (node (ref "U3") (pin "5") (pinfunction "VCC_5") (pintype "passive"))
      (node (ref "U4") (pin "8") (pinfunction "VCC_8") (pintype "passive"))
      (node (ref "U5") (pin "5") (pinfunction "VCC_5") (pintype "passive"))
      (node (ref "U6") (pin "5") (pinfunction "VCC_5") (pintype "passive"))
      (node (ref "U8") (pin "3") (pinfunction "VBUS/GND_3") (pintype "power_in"))
      (node (ref "U9") (pin "4") (pinfunction "VIN_SW_4") (pintype "input"))
      (node (ref "U9") (pin "5") (pinfunction "VIN_A_5") (pintype "input"))
      (node (ref "U9") (pin "6") (pinfunction "VINH_6") (pintype "input"))
    )
    (net (code "82") (name "VCCK10") (class "Default")
      (node (ref "C31") (pin "2") (pinfunction "2_2") (pintype "passive"))
      (node (ref "C38") (pin "2") (pinfunction "2_2") (pintype "passive"))
      (node (ref "C39") (pin "2") (pinfunction "2_2") (pintype "passive"))
      (node (ref "C40") (pin "2") (pinfunction "2_2") (pintype "passive"))
      (node (ref "C41") (pin "2") (pinfunction "2_2") (pintype "passive"))
      (node (ref "L2") (pin "2") (pinfunction "2_2") (pintype "passive"))
      (node (ref "R36") (pin "1") (pinfunction "1_1") (pintype "passive"))
      (node (ref "U7") (pin "24") (pinfunction "VCCK_24") (pintype "passive"))
      (node (ref "U7") (pin "30") (pinfunction "VCCK_30") (pintype "passive"))
      (node (ref "U7") (pin "31") (pinfunction "VCCK_31") (pintype "passive"))
      (node (ref "U7") (pin "32") (pinfunction "VCCK_32") (pintype "passive"))
      (node (ref "U7") (pin "57") (pinfunction "VCCK_57") (pintype "passive"))
      (node (ref "U7") (pin "58") (pinfunction "VCCK_58") (pintype "passive"))
    )
    (net (code "83") (name "unconnected-(IC1-EXTINT-Pad5)") (class "Default")
      (node (ref "IC1") (pin "5") (pinfunction "EXTINT_5") (pintype "passive+no_connect"))
    )
    (net (code "84") (name "unconnected-(IC1-LNA_EN-Pad13)") (class "Default")
      (node (ref "IC1") (pin "13") (pinfunction "LNA_EN_13") (pintype "passive+no_connect"))
    )
    (net (code "85") (name "unconnected-(IC1-RESET_N-Pad9)") (class "Default")
      (node (ref "IC1") (pin "9") (pinfunction "RESET_N_9") (pintype "passive+no_connect"))
    )
    (net (code "86") (name "unconnected-(IC1-VIO_SEL-Pad15)") (class "Default")
      (node (ref "IC1") (pin "15") (pinfunction "VIO_SEL_15") (pintype "passive+no_connect"))
    )
    (net (code "87") (name "unconnected-(IC1-V_BCKP-Pad6)") (class "Default")
      (node (ref "IC1") (pin "6") (pinfunction "V_BCKP_6") (pintype "passive+no_connect"))
    )
    (net (code "88") (name "unconnected-(IC2-EXTINT-Pad4)") (class "Default")
      (node (ref "IC2") (pin "4") (pinfunction "EXTINT_4") (pintype "passive+no_connect"))
    )
    (net (code "89") (name "unconnected-(IC2-LNA_EN-Pad14)") (class "Default")
      (node (ref "IC2") (pin "14") (pinfunction "LNA_EN_14") (pintype "passive+no_connect"))
    )
    (net (code "90") (name "unconnected-(IC2-RESERVED_1-Pad15)") (class "Default")
      (node (ref "IC2") (pin "15") (pinfunction "RESERVED_1_15") (pintype "passive+no_connect"))
    )
    (net (code "91") (name "unconnected-(IC2-RESERVED_2-Pad16)") (class "Default")
      (node (ref "IC2") (pin "16") (pinfunction "RESERVED_2_16") (pintype "passive+no_connect"))
    )
    (net (code "92") (name "unconnected-(IC2-RESERVED_3-Pad17)") (class "Default")
      (node (ref "IC2") (pin "17") (pinfunction "RESERVED_3_17") (pintype "passive+no_connect"))
    )
    (net (code "93") (name "unconnected-(IC2-RESET_N-Pad8)") (class "Default")
      (node (ref "IC2") (pin "8") (pinfunction "RESET_N_8") (pintype "passive+no_connect"))
    )
    (net (code "94") (name "unconnected-(IC2-USB_DM-Pad5)") (class "Default")
      (node (ref "IC2") (pin "5") (pinfunction "USB_DM_5") (pintype "passive+no_connect"))
    )
    (net (code "95") (name "unconnected-(IC2-USB_DP-Pad6)") (class "Default")
      (node (ref "IC2") (pin "6") (pinfunction "USB_DP_6") (pintype "passive+no_connect"))
    )
    (net (code "96") (name "unconnected-(IC2-V_BCKP-Pad22)") (class "Default")
      (node (ref "IC2") (pin "22") (pinfunction "V_BCKP_22") (pintype "passive+no_connect"))
    )
    (net (code "97") (name "unconnected-(J4-VCC-PadP9)") (class "Default")
      (node (ref "J4") (pin "P9") (pinfunction "VCC_P9") (pintype "passive+no_connect"))
    )
    (net (code "98") (name "unconnected-(J5-SBU1-PadA8)") (class "Default")
      (node (ref "J5") (pin "A8") (pinfunction "SBU1_A8") (pintype "passive+no_connect"))
    )
    (net (code "99") (name "unconnected-(J5-SBU2-PadB8)") (class "Default")
      (node (ref "J5") (pin "B8") (pinfunction "SBU2_B8") (pintype "passive+no_connect"))
    )
    (net (code "100") (name "unconnected-(U7-CKO-Pad18)") (class "Default")
      (node (ref "U7") (pin "18") (pinfunction "CKO_18") (pintype "passive+no_connect"))
    )
    (net (code "101") (name "unconnected-(U7-GPIO0(MDC)-Pad48)") (class "Default")
      (node (ref "U7") (pin "48") (pinfunction "GPIO0(MDC)_48") (pintype "passive+no_connect"))
    )
    (net (code "102") (name "unconnected-(U7-GPIO1(MDIO)-Pad49)") (class "Default")
      (node (ref "U7") (pin "49") (pinfunction "GPIO1(MDIO)_49") (pintype "passive+no_connect"))
    )
    (net (code "103") (name "unconnected-(U7-GPIO2-Pad22)") (class "Default")
      (node (ref "U7") (pin "22") (pinfunction "GPIO2_22") (pintype "passive+no_connect"))
    )
    (net (code "104") (name "unconnected-(U7-GPIO15(1588_TOD)-Pad47)") (class "Default")
      (node (ref "U7") (pin "47") (pinfunction "GPIO15(1588_TOD)_47") (pintype "passive+no_connect"))
    )
    (net (code "105") (name "unconnected-(U7-LX-Pad60)") (class "Default")
      (node (ref "U7") (pin "60") (pinfunction "LX_60") (pintype "passive+no_connect"))
    )
    (net (code "106") (name "unconnected-(U8-NC-Pad9)") (class "Default")
      (node (ref "U8") (pin "9") (pinfunction "NC_9") (pintype "passive+no_connect"))
    )
    (net (code "107") (name "unconnected-(U8-NC-Pad10)") (class "Default")
      (node (ref "U8") (pin "10") (pinfunction "NC_10") (pintype "passive+no_connect"))
    )
  )
)
